# TK90X.net
KiCad netlist of a schematic drawn in EAGLE
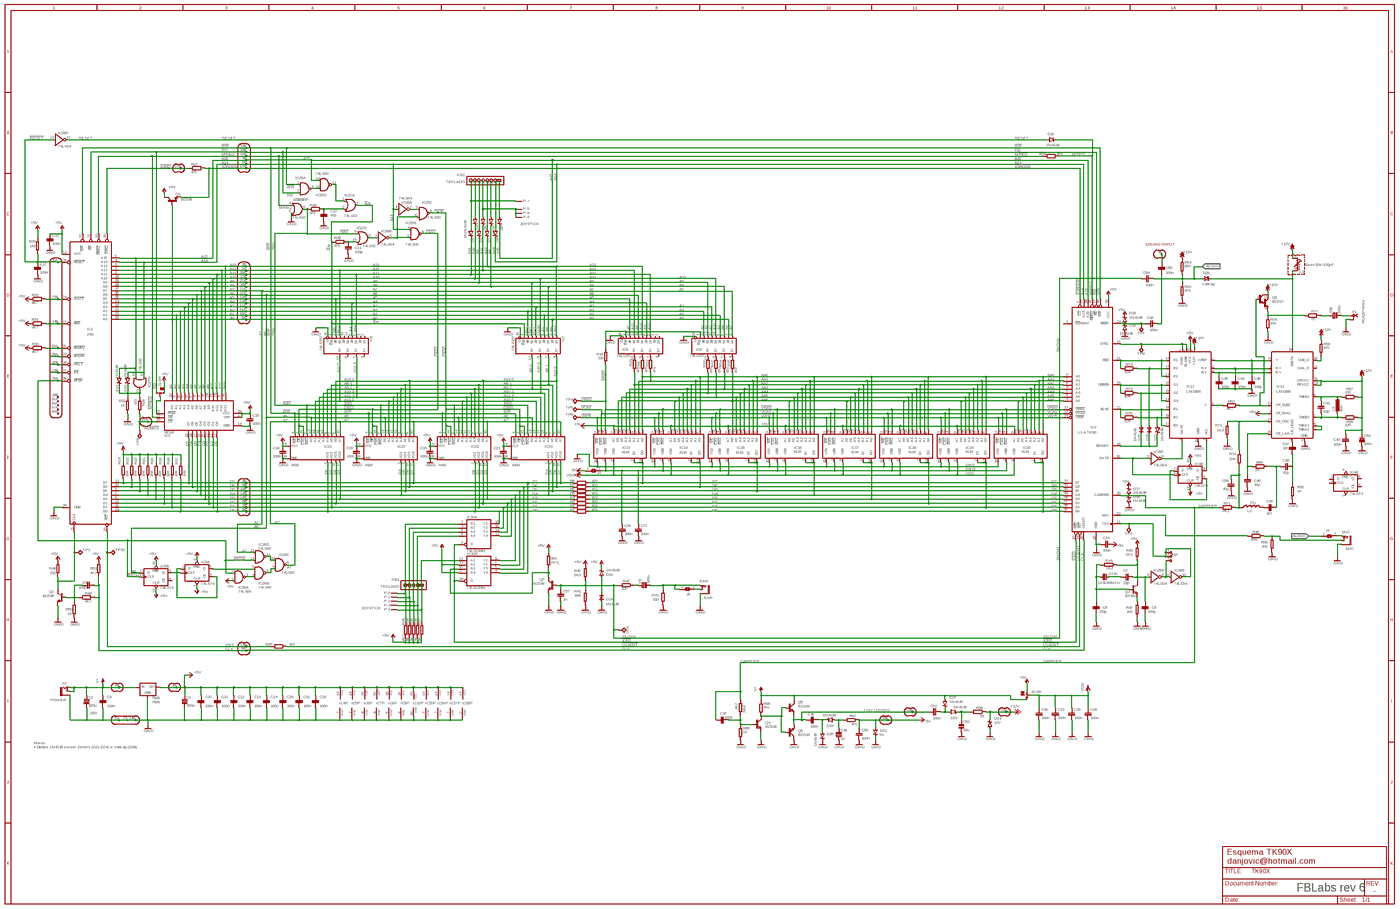
[diagram p0: schematic, sheet 1, overview]
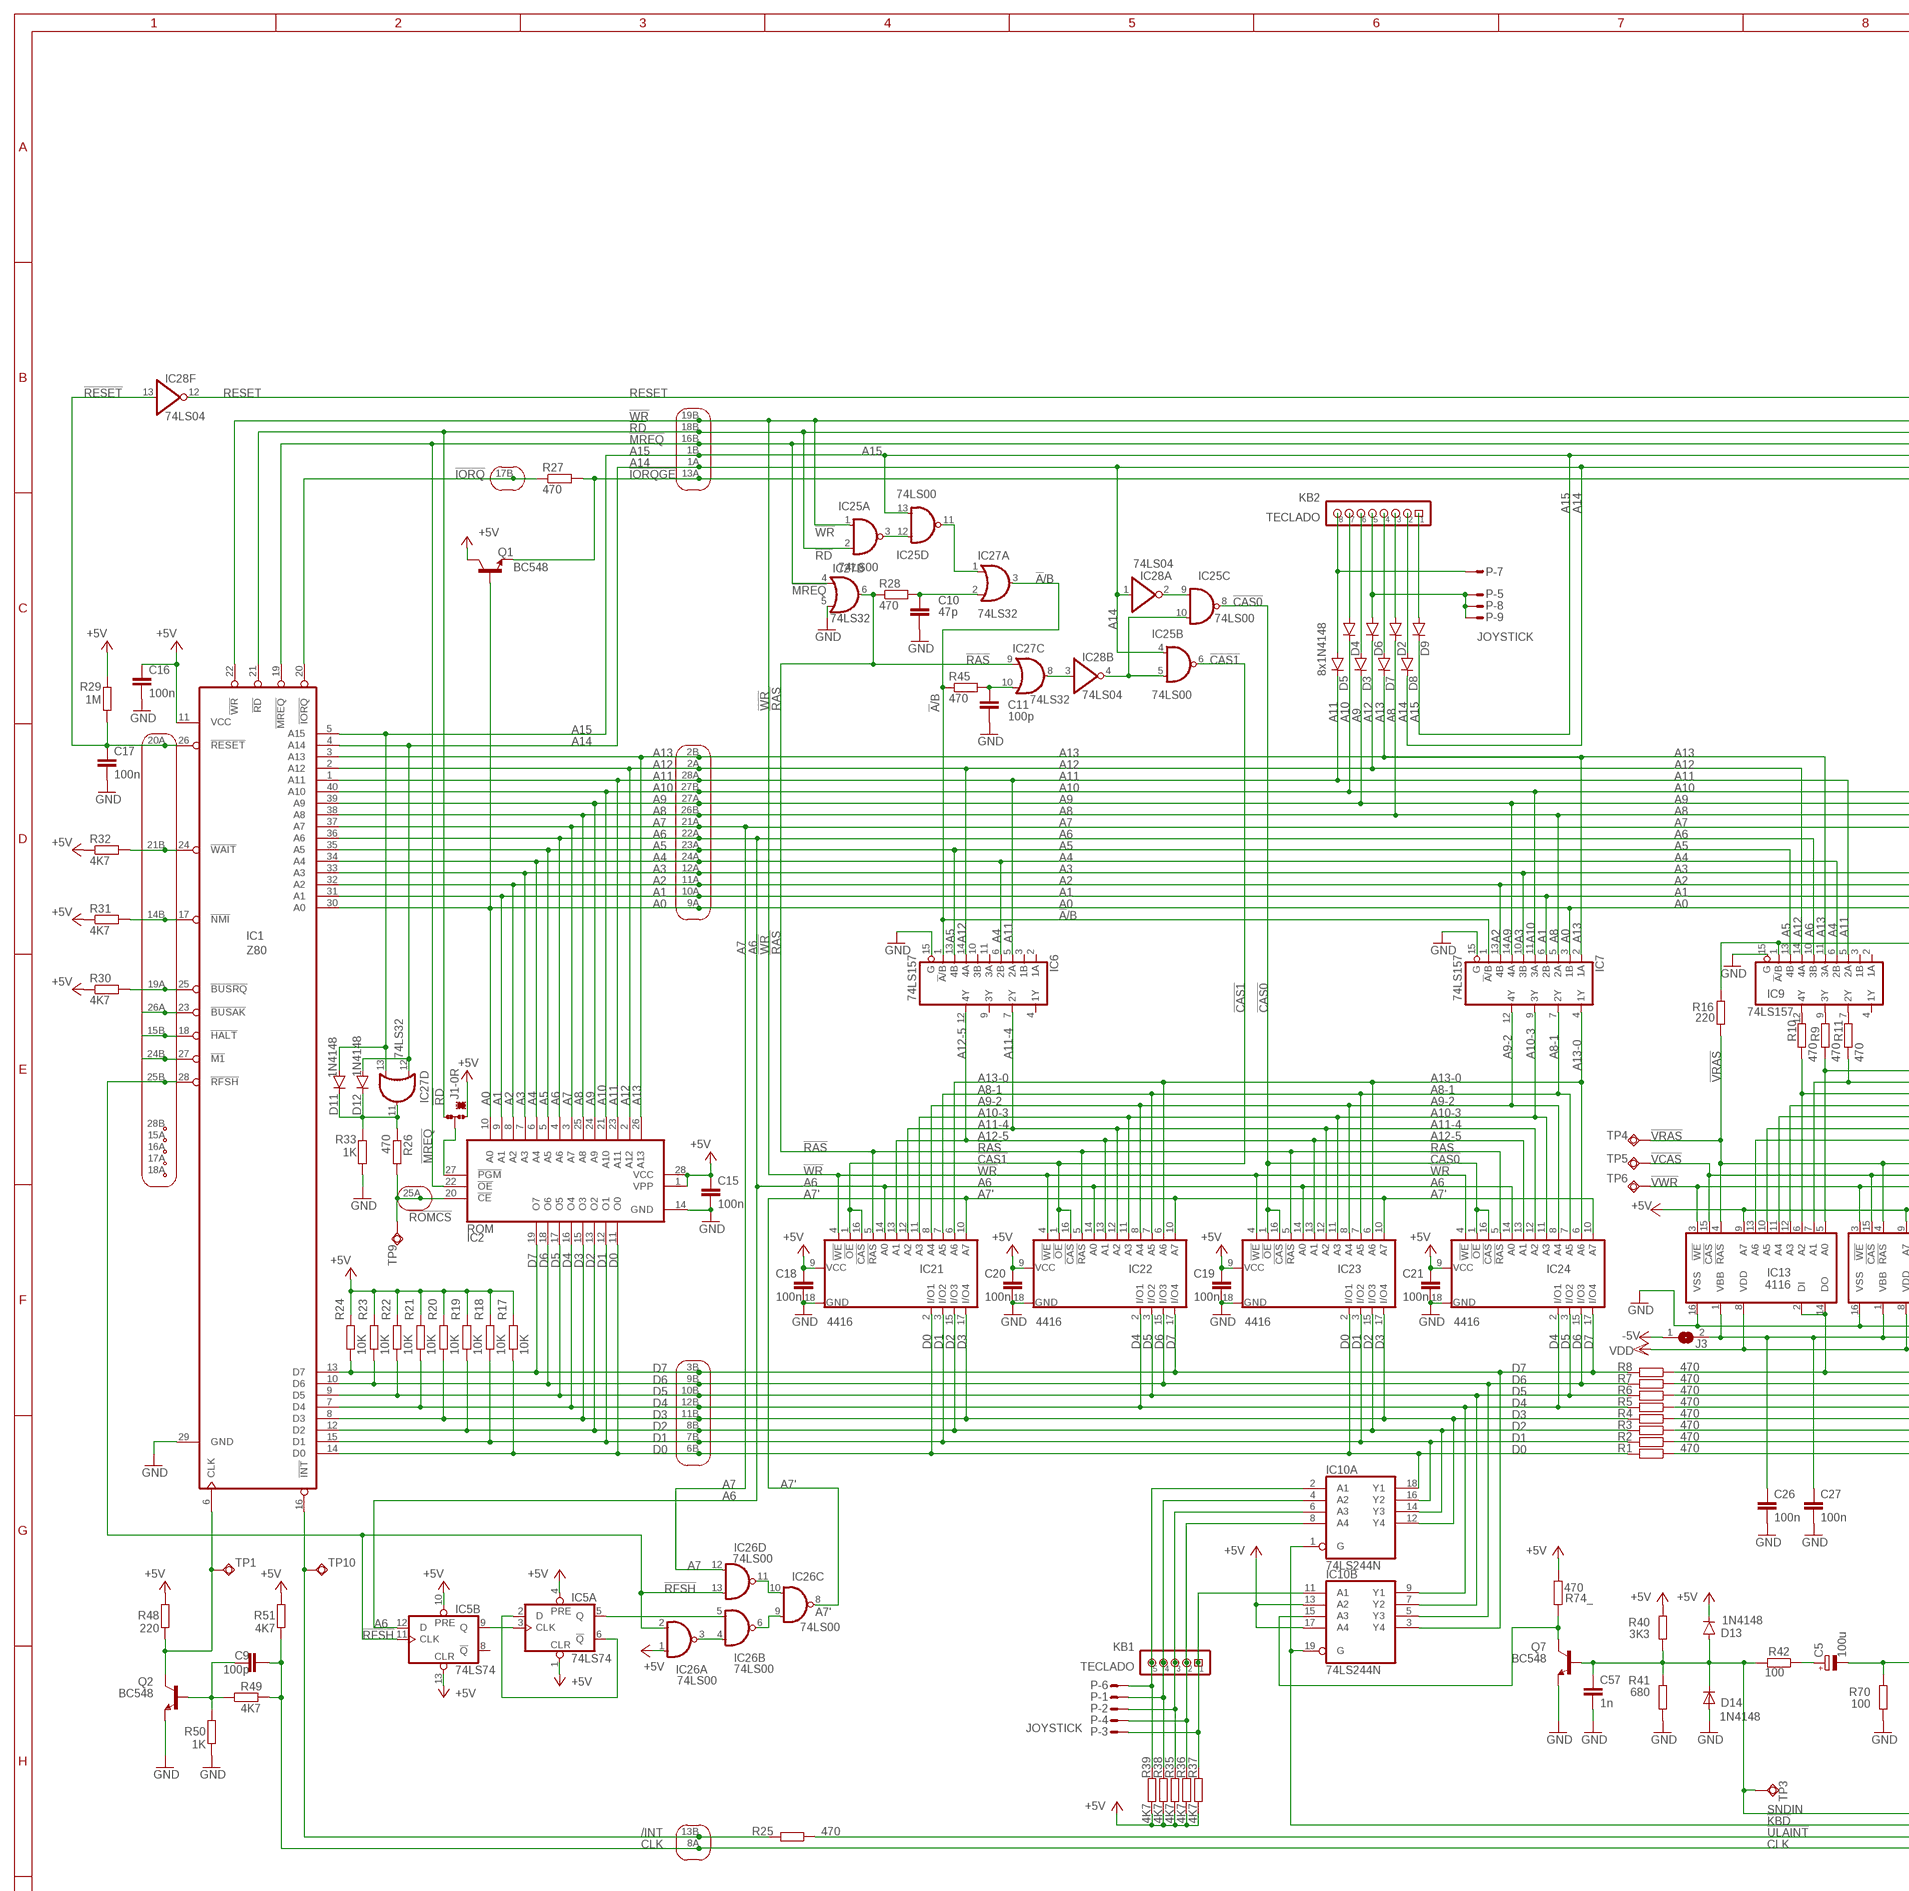
[diagram p1: schematic, sheet 1, part 1 of 4]
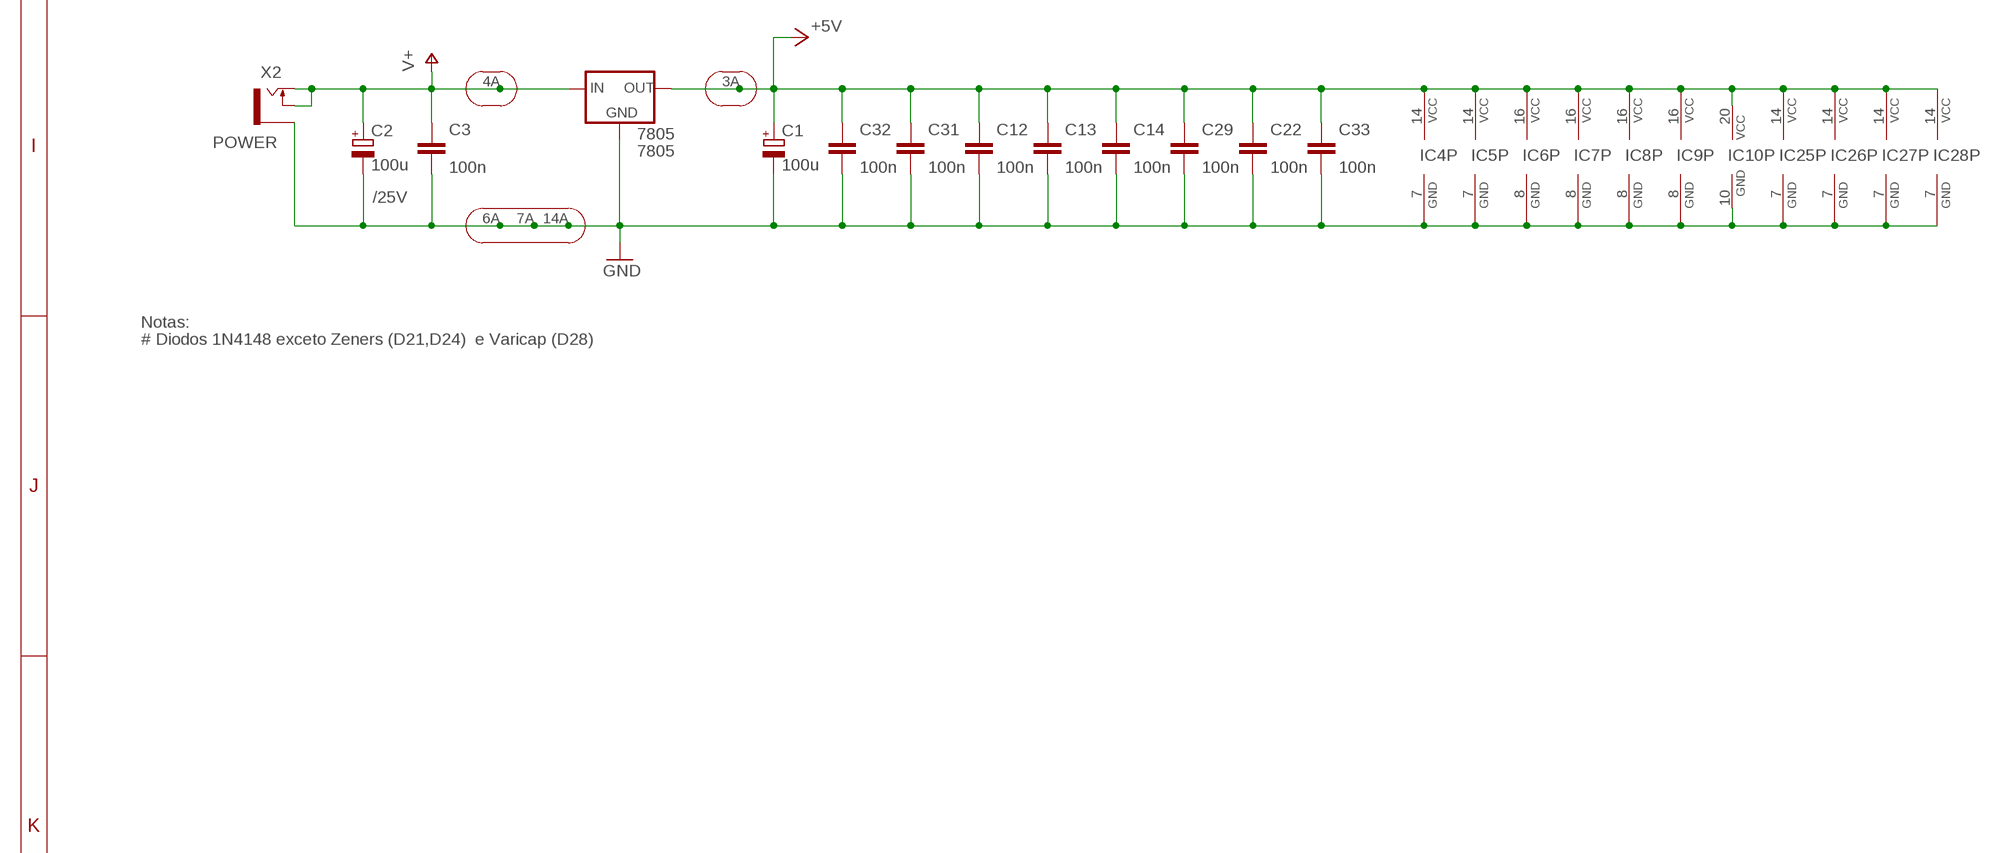
[diagram p2: schematic, sheet 1, part 2 of 4]
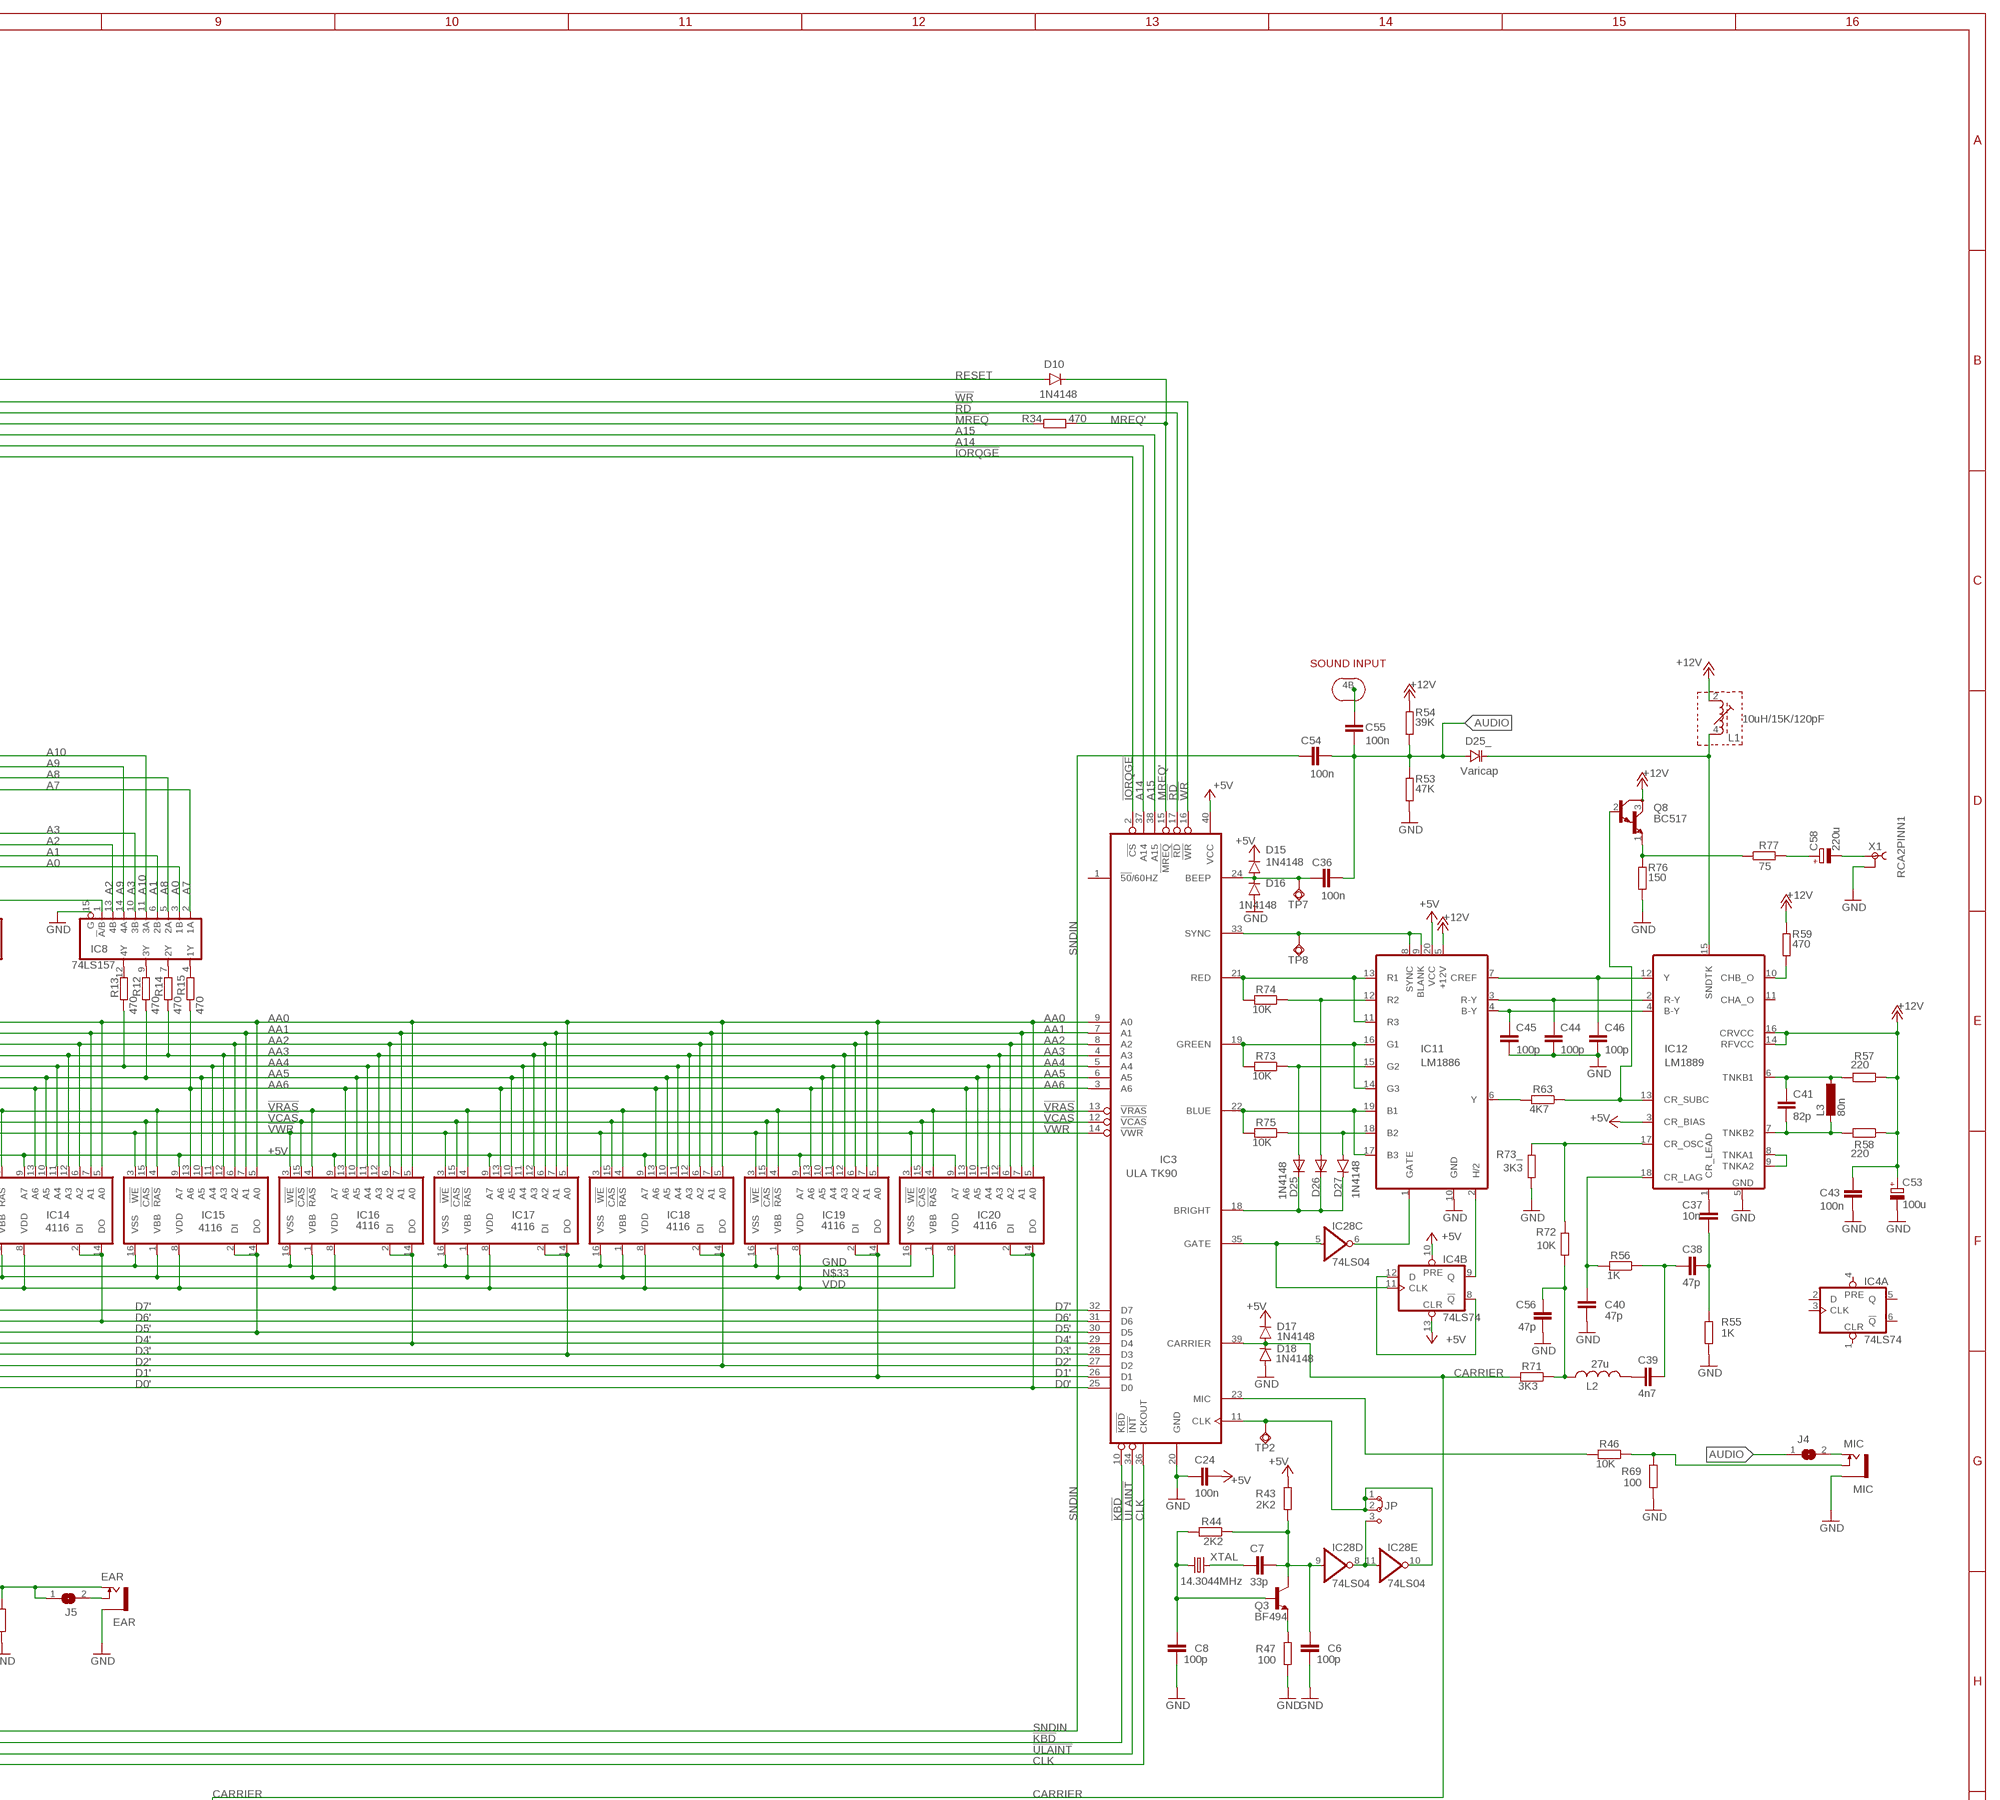
[diagram p3: schematic, sheet 1, part 3 of 4]
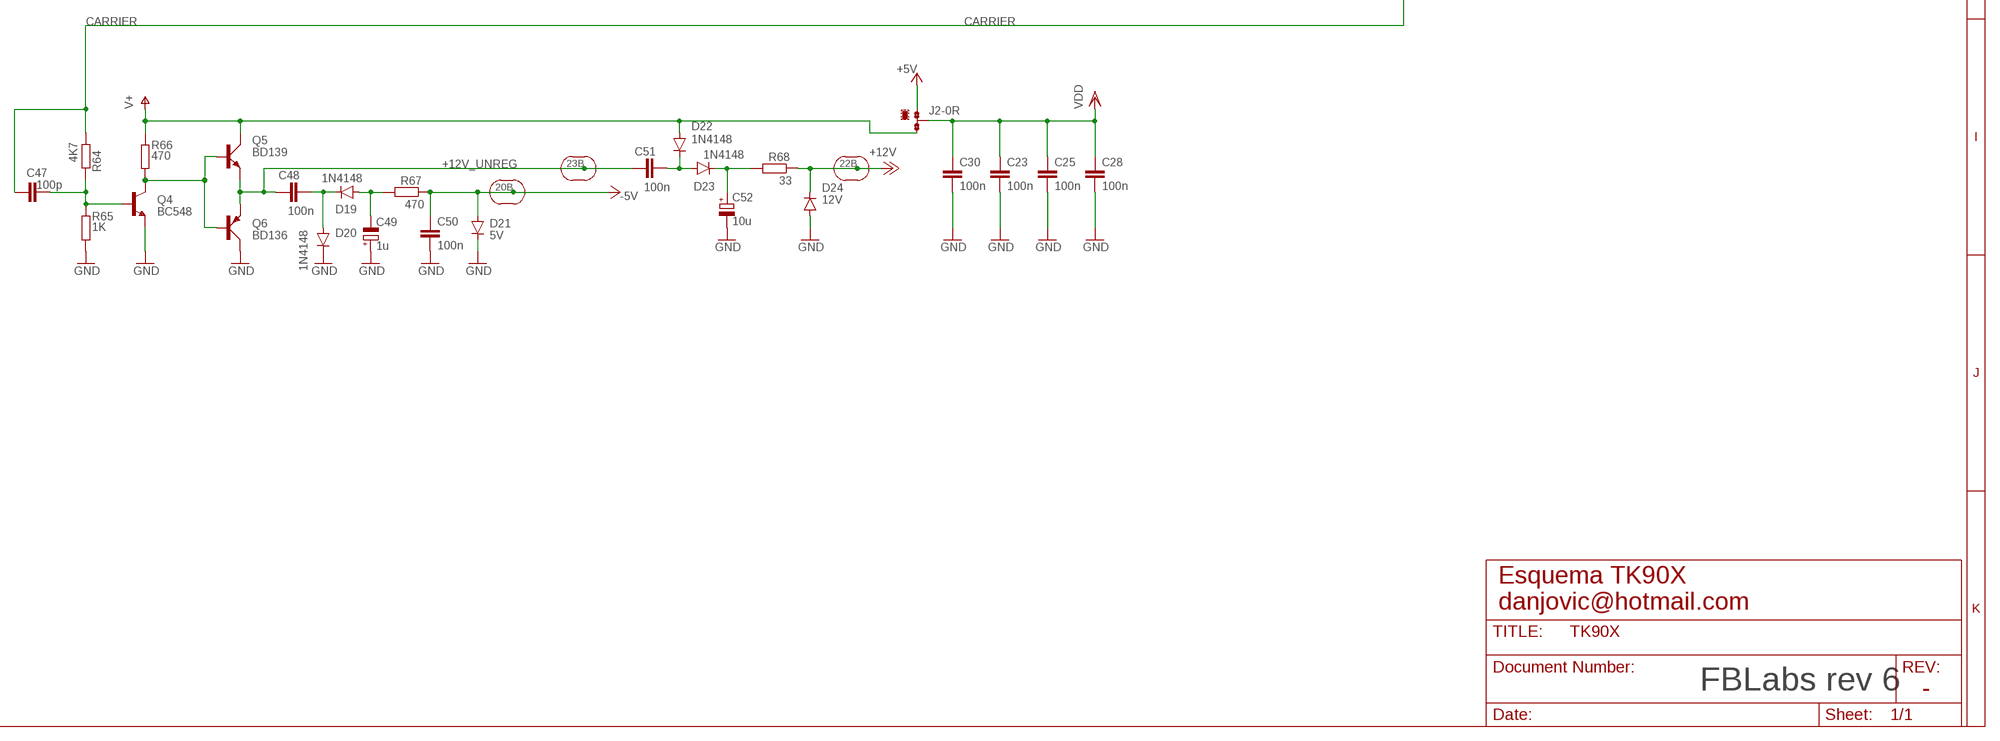
[diagram p4: schematic, sheet 1, part 4 of 4]

(export (version "E")
  (design (tool "Eeschema 10.0.6"))
  (components
    (comp (ref "7805")
      (value "7805")
      (footprint "eagle-import:78XXL")
      (libsource (lib "eagle-import") (part "78XXL"))
    )
    (comp (ref "C1")
      (value "100u")
      (footprint "eagle-import:E5-8,5")
      (libsource (lib "eagle-import") (part "CPOL-EUE5-8.5"))
    )
    (comp (ref "C2")
      (value "100u")
      (footprint "eagle-import:E5-8,5")
      (libsource (lib "eagle-import") (part "CPOL-EUE5-8.5"))
    )
    (comp (ref "C3")
      (value "100n")
      (footprint "eagle-import:C050-024X044")
      (libsource (lib "eagle-import") (part "C-EU050-024X044"))
    )
    (comp (ref "C5")
      (value "100u")
      (footprint "eagle-import:E5-4")
      (libsource (lib "eagle-import") (part "CPOL-EUE5-4"))
    )
    (comp (ref "C6")
      (value "100p")
      (footprint "eagle-import:C050-024X044")
      (libsource (lib "eagle-import") (part "C-EU050-024X044"))
    )
    (comp (ref "C7")
      (value "33p")
      (footprint "eagle-import:C050-024X044")
      (libsource (lib "eagle-import") (part "C-EU050-024X044"))
    )
    (comp (ref "C8")
      (value "100p")
      (footprint "eagle-import:C050-024X044")
      (libsource (lib "eagle-import") (part "C-EU050-024X044"))
    )
    (comp (ref "C9")
      (value "100p")
      (footprint "eagle-import:C050-024X044")
      (libsource (lib "eagle-import") (part "C-EU050-024X044"))
    )
    (comp (ref "C10")
      (value "47p")
      (footprint "eagle-import:C050-024X044")
      (libsource (lib "eagle-import") (part "C-EU050-024X044"))
    )
    (comp (ref "C11")
      (value "100p")
      (footprint "eagle-import:C050-024X044")
      (libsource (lib "eagle-import") (part "C-EU050-024X044"))
    )
    (comp (ref "C12")
      (value "100n")
      (footprint "eagle-import:C050-024X044")
      (libsource (lib "eagle-import") (part "C-EU050-024X044"))
    )
    (comp (ref "C13")
      (value "100n")
      (footprint "eagle-import:C050-024X044")
      (libsource (lib "eagle-import") (part "C-EU050-024X044"))
    )
    (comp (ref "C14")
      (value "100n")
      (footprint "eagle-import:C050-024X044")
      (libsource (lib "eagle-import") (part "C-EU050-024X044"))
    )
    (comp (ref "C15")
      (value "100n")
      (footprint "eagle-import:C050-024X044")
      (libsource (lib "eagle-import") (part "C-EU050-024X044"))
    )
    (comp (ref "C16")
      (value "100n")
      (footprint "eagle-import:C050-024X044")
      (libsource (lib "eagle-import") (part "C-EU050-024X044"))
    )
    (comp (ref "C17")
      (value "100n")
      (footprint "eagle-import:C050-024X044")
      (libsource (lib "eagle-import") (part "C-EU050-024X044"))
    )
    (comp (ref "C18")
      (value "100n")
      (footprint "eagle-import:C050-024X044")
      (libsource (lib "eagle-import") (part "C-EU050-024X044"))
    )
    (comp (ref "C19")
      (value "100n")
      (footprint "eagle-import:C050-024X044")
      (libsource (lib "eagle-import") (part "C-EU050-024X044"))
    )
    (comp (ref "C20")
      (value "100n")
      (footprint "eagle-import:C050-024X044")
      (libsource (lib "eagle-import") (part "C-EU050-024X044"))
    )
    (comp (ref "C21")
      (value "100n")
      (footprint "eagle-import:C050-024X044")
      (libsource (lib "eagle-import") (part "C-EU050-024X044"))
    )
    (comp (ref "C22")
      (value "100n")
      (footprint "eagle-import:C050-024X044")
      (libsource (lib "eagle-import") (part "C-EU050-024X044"))
    )
    (comp (ref "C23")
      (value "100n")
      (footprint "eagle-import:C050-024X044")
      (libsource (lib "eagle-import") (part "C-EU050-024X044"))
    )
    (comp (ref "C24")
      (value "100n")
      (footprint "eagle-import:C050-024X044")
      (libsource (lib "eagle-import") (part "C-EU050-024X044"))
    )
    (comp (ref "C25")
      (value "100n")
      (footprint "eagle-import:C050-024X044")
      (libsource (lib "eagle-import") (part "C-EU050-024X044"))
    )
    (comp (ref "C26")
      (value "100n")
      (footprint "eagle-import:C050-024X044")
      (libsource (lib "eagle-import") (part "C-EU050-024X044"))
    )
    (comp (ref "C27")
      (value "100n")
      (footprint "eagle-import:C050-024X044")
      (libsource (lib "eagle-import") (part "C-EU050-024X044"))
    )
    (comp (ref "C28")
      (value "100n")
      (footprint "eagle-import:C050-024X044")
      (libsource (lib "eagle-import") (part "C-EU050-024X044"))
    )
    (comp (ref "C29")
      (value "100n")
      (footprint "eagle-import:C050-024X044")
      (libsource (lib "eagle-import") (part "C-EU050-024X044"))
    )
    (comp (ref "C30")
      (value "100n")
      (footprint "eagle-import:C050-024X044")
      (libsource (lib "eagle-import") (part "C-EU050-024X044"))
    )
    (comp (ref "C31")
      (value "100n")
      (footprint "eagle-import:C050-024X044")
      (libsource (lib "eagle-import") (part "C-EU050-024X044"))
    )
    (comp (ref "C32")
      (value "100n")
      (footprint "eagle-import:C050-024X044")
      (libsource (lib "eagle-import") (part "C-EU050-024X044"))
    )
    (comp (ref "C33")
      (value "100n")
      (footprint "eagle-import:C050-024X044")
      (libsource (lib "eagle-import") (part "C-EU050-024X044"))
    )
    (comp (ref "C36")
      (value "100n")
      (footprint "eagle-import:C050-024X044")
      (libsource (lib "eagle-import") (part "C-EU050-024X044"))
    )
    (comp (ref "C37")
      (value "10n")
      (footprint "eagle-import:C050-024X044")
      (libsource (lib "eagle-import") (part "C-EU050-024X044"))
    )
    (comp (ref "C38")
      (value "47p")
      (footprint "eagle-import:C050-024X044")
      (libsource (lib "eagle-import") (part "C-EU050-024X044"))
    )
    (comp (ref "C39")
      (value "4n7")
      (footprint "eagle-import:C050-024X044")
      (libsource (lib "eagle-import") (part "C-EU050-024X044"))
    )
    (comp (ref "C40")
      (value "47p")
      (footprint "eagle-import:C050-024X044")
      (libsource (lib "eagle-import") (part "C-EU050-024X044"))
    )
    (comp (ref "C41")
      (value "82p")
      (footprint "eagle-import:C050-024X044")
      (libsource (lib "eagle-import") (part "C-EU050-024X044"))
    )
    (comp (ref "C43")
      (value "100n")
      (footprint "eagle-import:C050-024X044")
      (libsource (lib "eagle-import") (part "C-EU050-024X044"))
    )
    (comp (ref "C44")
      (value "100p")
      (footprint "eagle-import:C050-024X044")
      (libsource (lib "eagle-import") (part "C-EU050-024X044"))
    )
    (comp (ref "C45")
      (value "100p")
      (footprint "eagle-import:C050-024X044")
      (libsource (lib "eagle-import") (part "C-EU050-024X044"))
    )
    (comp (ref "C46")
      (value "100p")
      (footprint "eagle-import:C050-024X044")
      (libsource (lib "eagle-import") (part "C-EU050-024X044"))
    )
    (comp (ref "C47")
      (value "100p")
      (footprint "eagle-import:C050-024X044")
      (libsource (lib "eagle-import") (part "C-EU050-024X044"))
    )
    (comp (ref "C48")
      (value "100n")
      (footprint "eagle-import:C050-024X044")
      (libsource (lib "eagle-import") (part "C-EU050-024X044"))
    )
    (comp (ref "C49")
      (value "1u")
      (footprint "eagle-import:E2-4")
      (libsource (lib "eagle-import") (part "CPOL-EUE2-4"))
    )
    (comp (ref "C50")
      (value "100n")
      (footprint "eagle-import:C050-024X044")
      (libsource (lib "eagle-import") (part "C-EU050-024X044"))
    )
    (comp (ref "C51")
      (value "100n")
      (footprint "eagle-import:C050-024X044")
      (libsource (lib "eagle-import") (part "C-EU050-024X044"))
    )
    (comp (ref "C52")
      (value "10u")
      (footprint "eagle-import:E2-5")
      (libsource (lib "eagle-import") (part "CPOL-EUE2-5"))
    )
    (comp (ref "C53")
      (value "100u")
      (footprint "eagle-import:E5-4")
      (libsource (lib "eagle-import") (part "CPOL-EUE5-4"))
    )
    (comp (ref "C54")
      (value "100n")
      (footprint "eagle-import:C050-024X044")
      (libsource (lib "eagle-import") (part "C-EU050-024X044"))
    )
    (comp (ref "C55")
      (value "100n")
      (footprint "eagle-import:C050-024X044")
      (libsource (lib "eagle-import") (part "C-EU050-024X044"))
    )
    (comp (ref "C56")
      (value "47p")
      (footprint "eagle-import:C050-024X044")
      (libsource (lib "eagle-import") (part "C-EU050-024X044"))
    )
    (comp (ref "C57")
      (value "1n")
      (footprint "eagle-import:C050-024X044")
      (libsource (lib "eagle-import") (part "C-EU050-024X044"))
    )
    (comp (ref "C58")
      (value "220u")
      (footprint "eagle-import:E5-6")
      (libsource (lib "eagle-import") (part "CPOL-EUE5-6"))
    )
    (comp (ref "D2")
      (value "1N4148")
      (footprint "eagle-import:DO35-12")
      (libsource (lib "eagle-import") (part "DDO35-12"))
    )
    (comp (ref "D3")
      (value "1N4148")
      (footprint "eagle-import:DO35-12")
      (libsource (lib "eagle-import") (part "DDO35-12"))
    )
    (comp (ref "D4")
      (value "1N4148")
      (footprint "eagle-import:DO35-12")
      (libsource (lib "eagle-import") (part "DDO35-12"))
    )
    (comp (ref "D5")
      (value "1N4148")
      (footprint "eagle-import:DO35-12")
      (libsource (lib "eagle-import") (part "DDO35-12"))
    )
    (comp (ref "D6")
      (value "1N4148")
      (footprint "eagle-import:DO35-12")
      (libsource (lib "eagle-import") (part "DDO35-12"))
    )
    (comp (ref "D7")
      (value "1N4148")
      (footprint "eagle-import:DO35-12")
      (libsource (lib "eagle-import") (part "DDO35-12"))
    )
    (comp (ref "D8")
      (value "1N4148")
      (footprint "eagle-import:DO35-12")
      (libsource (lib "eagle-import") (part "DDO35-12"))
    )
    (comp (ref "D9")
      (value "1N4148")
      (footprint "eagle-import:DO35-12")
      (libsource (lib "eagle-import") (part "DDO35-12"))
    )
    (comp (ref "D10")
      (value "1N4148")
      (footprint "eagle-import:DO35-12")
      (libsource (lib "eagle-import") (part "DDO35-12"))
    )
    (comp (ref "D11")
      (value "1N4148")
      (footprint "eagle-import:DO35-12")
      (libsource (lib "eagle-import") (part "DDO35-12"))
    )
    (comp (ref "D12")
      (value "1N4148")
      (footprint "eagle-import:DO35-12")
      (libsource (lib "eagle-import") (part "DDO35-12"))
    )
    (comp (ref "D13")
      (value "1N4148")
      (footprint "eagle-import:DO35-12")
      (libsource (lib "eagle-import") (part "DDO35-12"))
    )
    (comp (ref "D14")
      (value "1N4148")
      (footprint "eagle-import:D-5")
      (libsource (lib "eagle-import") (part "DIODE-D-5"))
    )
    (comp (ref "D15")
      (value "1N4148")
      (footprint "eagle-import:DO35-12")
      (libsource (lib "eagle-import") (part "DDO35-12"))
    )
    (comp (ref "D16")
      (value "1N4148")
      (footprint "eagle-import:DO35-12")
      (libsource (lib "eagle-import") (part "DDO35-12"))
    )
    (comp (ref "D17")
      (value "1N4148")
      (footprint "eagle-import:DO35-12")
      (libsource (lib "eagle-import") (part "DDO35-12"))
    )
    (comp (ref "D18")
      (value "1N4148")
      (footprint "eagle-import:DO35-12")
      (libsource (lib "eagle-import") (part "DDO35-12"))
    )
    (comp (ref "D19")
      (value "1N4148")
      (footprint "eagle-import:DO35-12")
      (libsource (lib "eagle-import") (part "DDO35-12"))
    )
    (comp (ref "D20")
      (value "1N4148")
      (footprint "eagle-import:DO35-12")
      (libsource (lib "eagle-import") (part "DDO35-12"))
    )
    (comp (ref "D21")
      (value "5V")
      (footprint "eagle-import:DO35-12")
      (libsource (lib "eagle-import") (part "DDO35-12"))
    )
    (comp (ref "D22")
      (value "1N4148")
      (footprint "eagle-import:DO35-12")
      (libsource (lib "eagle-import") (part "DDO35-12"))
    )
    (comp (ref "D23")
      (value "1N4148")
      (footprint "eagle-import:DO35-12")
      (libsource (lib "eagle-import") (part "DDO35-12"))
    )
    (comp (ref "D24")
      (value "12V")
      (footprint "eagle-import:DO35-12")
      (libsource (lib "eagle-import") (part "DDO35-12"))
    )
    (comp (ref "D25")
      (value "1N4148")
      (footprint "eagle-import:D-5")
      (libsource (lib "eagle-import") (part "DIODE-D-5"))
    )
    (comp (ref "D25_")
      (value "Varicap")
      (footprint "eagle-import:D200")
      (libsource (lib "eagle-import") (part "VARICAP-200"))
    )
    (comp (ref "D26")
      (value "1N4148")
      (footprint "eagle-import:D-5")
      (libsource (lib "eagle-import") (part "DIODE-D-5"))
    )
    (comp (ref "D27")
      (value "1N4148")
      (footprint "eagle-import:DO35-12")
      (libsource (lib "eagle-import") (part "DDO35-12"))
    )
    (comp (ref "EAR")
      (value "EAR")
      (footprint "eagle-import:MONO")
      (libsource (lib "eagle-import") (part "JACK?-MONO"))
    )
    (comp (ref "IC1")
      (value "Z80")
      (footprint "eagle-import:DIL40")
      (libsource (lib "eagle-import") (part "Z80CPU"))
    )
    (comp (ref "IC2")
      (value "ROM")
      (footprint "eagle-import:DIL28")
      (libsource (lib "eagle-import") (part "25128"))
    )
    (comp (ref "IC3")
      (value "ULA TK90")
      (footprint "eagle-import:DIL40")
      (libsource (lib "eagle-import") (part "ULA-TK90"))
    )
    (comp (ref "IC4")
      (value "74LS74")
      (footprint "eagle-import:DIL14")
      (libsource (lib "eagle-import") (part "7474NLS"))
    )
    (comp (ref "IC5")
      (value "74LS74")
      (footprint "eagle-import:DIL14")
      (libsource (lib "eagle-import") (part "7474NLS"))
    )
    (comp (ref "IC6")
      (value "74LS157")
      (footprint "eagle-import:DIL16")
      (libsource (lib "eagle-import") (part "74157NS"))
    )
    (comp (ref "IC7")
      (value "74LS157")
      (footprint "eagle-import:DIL16")
      (libsource (lib "eagle-import") (part "74157NS"))
    )
    (comp (ref "IC8")
      (value "74LS157")
      (footprint "eagle-import:DIL16")
      (libsource (lib "eagle-import") (part "74157NS"))
    )
    (comp (ref "IC9")
      (value "74LS157")
      (footprint "eagle-import:DIL16")
      (libsource (lib "eagle-import") (part "74157NS"))
    )
    (comp (ref "IC10")
      (value "74LS244N")
      (footprint "eagle-import:DIL20")
      (libsource (lib "eagle-import") (part "74244NLS"))
    )
    (comp (ref "IC11")
      (value "LM1886")
      (footprint "eagle-import:DIL20")
      (libsource (lib "eagle-import") (part "LM1886N"))
    )
    (comp (ref "IC12")
      (value "LM1889")
      (footprint "eagle-import:DIL18")
      (libsource (lib "eagle-import") (part "LM1889"))
    )
    (comp (ref "IC13")
      (value "4116")
      (footprint "eagle-import:DIL16")
      (libsource (lib "eagle-import") (part "MK4516"))
    )
    (comp (ref "IC14")
      (value "4116")
      (footprint "eagle-import:DIL16")
      (libsource (lib "eagle-import") (part "MK4516"))
    )
    (comp (ref "IC15")
      (value "4116")
      (footprint "eagle-import:DIL16")
      (libsource (lib "eagle-import") (part "MK4516"))
    )
    (comp (ref "IC16")
      (value "4116")
      (footprint "eagle-import:DIL16")
      (libsource (lib "eagle-import") (part "MK4516"))
    )
    (comp (ref "IC17")
      (value "4116")
      (footprint "eagle-import:DIL16")
      (libsource (lib "eagle-import") (part "MK4516"))
    )
    (comp (ref "IC18")
      (value "4116")
      (footprint "eagle-import:DIL16")
      (libsource (lib "eagle-import") (part "MK4516"))
    )
    (comp (ref "IC19")
      (value "4116")
      (footprint "eagle-import:DIL16")
      (libsource (lib "eagle-import") (part "MK4516"))
    )
    (comp (ref "IC20")
      (value "4116")
      (footprint "eagle-import:DIL16")
      (libsource (lib "eagle-import") (part "MK4516"))
    )
    (comp (ref "IC21")
      (value "4416")
      (footprint "eagle-import:DIL18")
      (libsource (lib "eagle-import") (part "4416"))
    )
    (comp (ref "IC22")
      (value "4416")
      (footprint "eagle-import:DIL18")
      (libsource (lib "eagle-import") (part "4416"))
    )
    (comp (ref "IC23")
      (value "4416")
      (footprint "eagle-import:DIL18")
      (libsource (lib "eagle-import") (part "4416"))
    )
    (comp (ref "IC24")
      (value "4416")
      (footprint "eagle-import:DIL18")
      (libsource (lib "eagle-import") (part "4416"))
    )
    (comp (ref "IC25")
      (value "74LS00")
      (footprint "eagle-import:DIL14")
      (libsource (lib "eagle-import") (part "7400NLS"))
    )
    (comp (ref "IC26")
      (value "74LS00")
      (footprint "eagle-import:DIL14")
      (libsource (lib "eagle-import") (part "7400NLS"))
    )
    (comp (ref "IC27")
      (value "74LS32")
      (footprint "eagle-import:DIL14")
      (libsource (lib "eagle-import") (part "7432NLS"))
    )
    (comp (ref "IC28")
      (value "74LS04")
      (footprint "eagle-import:DIL14")
      (libsource (lib "eagle-import") (part "7404NLS"))
    )
    (comp (ref "J1")
      (value "0R-JUMPB")
      (footprint "eagle-import:B0R-JMP")
      (libsource (lib "eagle-import") (part "0R-JUMPB"))
    )
    (comp (ref "J2")
      (value "0R-JUMPB")
      (footprint "eagle-import:B0R-JMP")
      (libsource (lib "eagle-import") (part "0R-JUMPB"))
    )
    (comp (ref "J3") (value "SJ") (footprint "eagle-import:SJ") (libsource (lib "eagle-import") (part "SJ")))
    (comp (ref "J4") (value "SJ") (footprint "eagle-import:SJ") (libsource (lib "eagle-import") (part "SJ")))
    (comp (ref "J5") (value "SJ") (footprint "eagle-import:SJ") (libsource (lib "eagle-import") (part "SJ")))
    (comp (ref "JP")
      (value "J2X1MM")
      (footprint "eagle-import:03C")
      (libsource (lib "eagle-import") (part "J2X1MM"))
    )
    (comp (ref "KB1")
      (value "TECLADO")
      (footprint "eagle-import:FE05-1")
      (libsource (lib "eagle-import") (part "CON-TECL-5"))
    )
    (comp (ref "KB2")
      (value "TECLADO")
      (footprint "eagle-import:FE08")
      (libsource (lib "eagle-import") (part "CON-TECL-8"))
    )
    (comp (ref "L1")
      (value "10uH/15K/120pF")
      (footprint "eagle-import:COIL")
      (libsource (lib "eagle-import") (part "COIL"))
    )
    (comp (ref "L2")
      (value "27u")
      (footprint "eagle-import:0207_7")
      (libsource (lib "eagle-import") (part "L-US0207/7"))
    )
    (comp (ref "L3")
      (value "80n")
      (footprint "eagle-import:0204_5")
      (libsource (lib "eagle-import") (part "L-EU0204/5"))
    )
    (comp (ref "MIC")
      (value "MIC")
      (footprint "eagle-import:MONO")
      (libsource (lib "eagle-import") (part "JACK?-MONO"))
    )
    (comp (ref "P")
      (value "JOYSTICK")
      (footprint "eagle-import:177-009-MALE")
      (libsource (lib "eagle-import") (part "M09?S.590"))
    )
    (comp (ref "Q1")
      (value "BC548")
      (footprint "eagle-import:TO92L")
      (libsource (lib "eagle-import") (part "-NPN-TO92L"))
    )
    (comp (ref "Q2")
      (value "BC548")
      (footprint "eagle-import:TO92L")
      (libsource (lib "eagle-import") (part "-NPN-TO92L"))
    )
    (comp (ref "Q3")
      (value "BF494")
      (footprint "eagle-import:TO92-CEB")
      (libsource (lib "eagle-import") (part "BF494"))
    )
    (comp (ref "Q4")
      (value "BC548")
      (footprint "eagle-import:TO92L")
      (libsource (lib "eagle-import") (part "-NPN-TO92L"))
    )
    (comp (ref "Q5")
      (value "BD139")
      (footprint "eagle-import:TO126AV")
      (libsource (lib "eagle-import") (part "BD139"))
    )
    (comp (ref "Q6")
      (value "BD136")
      (footprint "eagle-import:TO126AV")
      (libsource (lib "eagle-import") (part "BD140"))
    )
    (comp (ref "Q7")
      (value "BC548")
      (footprint "eagle-import:TO92L")
      (libsource (lib "eagle-import") (part "-NPN-TO92L"))
    )
    (comp (ref "Q8")
      (value "BC517")
      (footprint "eagle-import:TO92")
      (libsource (lib "eagle-import") (part "BC517"))
    )
    (comp (ref "R1")
      (value "470")
      (footprint "eagle-import:0207_12")
      (libsource (lib "eagle-import") (part "R-EU_0207/12"))
    )
    (comp (ref "R2")
      (value "470")
      (footprint "eagle-import:0207_12")
      (libsource (lib "eagle-import") (part "R-EU_0207/12"))
    )
    (comp (ref "R3")
      (value "470")
      (footprint "eagle-import:0207_12")
      (libsource (lib "eagle-import") (part "R-EU_0207/12"))
    )
    (comp (ref "R4")
      (value "470")
      (footprint "eagle-import:0207_12")
      (libsource (lib "eagle-import") (part "R-EU_0207/12"))
    )
    (comp (ref "R5")
      (value "470")
      (footprint "eagle-import:0207_12")
      (libsource (lib "eagle-import") (part "R-EU_0207/12"))
    )
    (comp (ref "R6")
      (value "470")
      (footprint "eagle-import:0207_12")
      (libsource (lib "eagle-import") (part "R-EU_0207/12"))
    )
    (comp (ref "R7")
      (value "470")
      (footprint "eagle-import:0207_12")
      (libsource (lib "eagle-import") (part "R-EU_0207/12"))
    )
    (comp (ref "R8")
      (value "470")
      (footprint "eagle-import:0207_12")
      (libsource (lib "eagle-import") (part "R-EU_0207/12"))
    )
    (comp (ref "R9")
      (value "470")
      (footprint "eagle-import:0207_12")
      (libsource (lib "eagle-import") (part "R-EU_0207/12"))
    )
    (comp (ref "R10")
      (value "470")
      (footprint "eagle-import:0207_12")
      (libsource (lib "eagle-import") (part "R-EU_0207/12"))
    )
    (comp (ref "R11")
      (value "470")
      (footprint "eagle-import:0207_12")
      (libsource (lib "eagle-import") (part "R-EU_0207/12"))
    )
    (comp (ref "R12")
      (value "470")
      (footprint "eagle-import:0207_12")
      (libsource (lib "eagle-import") (part "R-EU_0207/12"))
    )
    (comp (ref "R13")
      (value "470")
      (footprint "eagle-import:0207_12")
      (libsource (lib "eagle-import") (part "R-EU_0207/12"))
    )
    (comp (ref "R14")
      (value "470")
      (footprint "eagle-import:0207_12")
      (libsource (lib "eagle-import") (part "R-EU_0207/12"))
    )
    (comp (ref "R15")
      (value "470")
      (footprint "eagle-import:0207_12")
      (libsource (lib "eagle-import") (part "R-EU_0207/12"))
    )
    (comp (ref "R16")
      (value "220")
      (footprint "eagle-import:0207_12")
      (libsource (lib "eagle-import") (part "R-EU_0207/12"))
    )
    (comp (ref "R17")
      (value "10K")
      (footprint "eagle-import:0207_12")
      (libsource (lib "eagle-import") (part "R-EU_0207/12"))
    )
    (comp (ref "R18")
      (value "10K")
      (footprint "eagle-import:0207_12")
      (libsource (lib "eagle-import") (part "R-EU_0207/12"))
    )
    (comp (ref "R19")
      (value "10K")
      (footprint "eagle-import:0207_12")
      (libsource (lib "eagle-import") (part "R-EU_0207/12"))
    )
    (comp (ref "R20")
      (value "10K")
      (footprint "eagle-import:0207_12")
      (libsource (lib "eagle-import") (part "R-EU_0207/12"))
    )
    (comp (ref "R21")
      (value "10K")
      (footprint "eagle-import:0207_12")
      (libsource (lib "eagle-import") (part "R-EU_0207/12"))
    )
    (comp (ref "R22")
      (value "10K")
      (footprint "eagle-import:0207_12")
      (libsource (lib "eagle-import") (part "R-EU_0207/12"))
    )
    (comp (ref "R23")
      (value "10K")
      (footprint "eagle-import:0207_12")
      (libsource (lib "eagle-import") (part "R-EU_0207/12"))
    )
    (comp (ref "R24")
      (value "10K")
      (footprint "eagle-import:0207_12")
      (libsource (lib "eagle-import") (part "R-EU_0207/12"))
    )
    (comp (ref "R25")
      (value "470")
      (footprint "eagle-import:0207_12")
      (libsource (lib "eagle-import") (part "R-EU_0207/12"))
    )
    (comp (ref "R26")
      (value "470")
      (footprint "eagle-import:0207_12")
      (libsource (lib "eagle-import") (part "R-EU_0207/12"))
    )
    (comp (ref "R27")
      (value "470")
      (footprint "eagle-import:0207_12")
      (libsource (lib "eagle-import") (part "R-EU_0207/12"))
    )
    (comp (ref "R28")
      (value "470")
      (footprint "eagle-import:0207_12")
      (libsource (lib "eagle-import") (part "R-EU_0207/12"))
    )
    (comp (ref "R29")
      (value "1M")
      (footprint "eagle-import:0207_12")
      (libsource (lib "eagle-import") (part "R-EU_0207/12"))
    )
    (comp (ref "R30")
      (value "4K7")
      (footprint "eagle-import:0207_12")
      (libsource (lib "eagle-import") (part "R-EU_0207/12"))
    )
    (comp (ref "R31")
      (value "4K7")
      (footprint "eagle-import:0207_12")
      (libsource (lib "eagle-import") (part "R-EU_0207/12"))
    )
    (comp (ref "R32")
      (value "4K7")
      (footprint "eagle-import:0207_12")
      (libsource (lib "eagle-import") (part "R-EU_0207/12"))
    )
    (comp (ref "R33")
      (value "1K")
      (footprint "eagle-import:0207_12")
      (libsource (lib "eagle-import") (part "R-EU_0207/12"))
    )
    (comp (ref "R34")
      (value "470")
      (footprint "eagle-import:0207_12")
      (libsource (lib "eagle-import") (part "R-EU_0207/12"))
    )
    (comp (ref "R35")
      (value "4K7")
      (footprint "eagle-import:0207_12")
      (libsource (lib "eagle-import") (part "R-EU_0207/12"))
    )
    (comp (ref "R36")
      (value "4K7")
      (footprint "eagle-import:0207_12")
      (libsource (lib "eagle-import") (part "R-EU_0207/12"))
    )
    (comp (ref "R37")
      (value "4K7")
      (footprint "eagle-import:0207_12")
      (libsource (lib "eagle-import") (part "R-EU_0207/12"))
    )
    (comp (ref "R38")
      (value "4K7")
      (footprint "eagle-import:0207_12")
      (libsource (lib "eagle-import") (part "R-EU_0207/12"))
    )
    (comp (ref "R39")
      (value "4K7")
      (footprint "eagle-import:0207_12")
      (libsource (lib "eagle-import") (part "R-EU_0207/12"))
    )
    (comp (ref "R40")
      (value "3K3")
      (footprint "eagle-import:0207_12")
      (libsource (lib "eagle-import") (part "R-EU_0207/12"))
    )
    (comp (ref "R41")
      (value "680")
      (footprint "eagle-import:0207_5V")
      (libsource (lib "eagle-import") (part "R-EU_0207/5V"))
    )
    (comp (ref "R42")
      (value "100")
      (footprint "eagle-import:0207_5V")
      (libsource (lib "eagle-import") (part "R-EU_0207/5V"))
    )
    (comp (ref "R43")
      (value "2K2")
      (footprint "eagle-import:0207_12")
      (libsource (lib "eagle-import") (part "R-EU_0207/12"))
    )
    (comp (ref "R44")
      (value "2K2")
      (footprint "eagle-import:0207_12")
      (libsource (lib "eagle-import") (part "R-EU_0207/12"))
    )
    (comp (ref "R45")
      (value "470")
      (footprint "eagle-import:0207_12")
      (libsource (lib "eagle-import") (part "R-EU_0207/12"))
    )
    (comp (ref "R46")
      (value "10K")
      (footprint "eagle-import:0207_12")
      (libsource (lib "eagle-import") (part "R-EU_0207/12"))
    )
    (comp (ref "R47")
      (value "100")
      (footprint "eagle-import:0207_12")
      (libsource (lib "eagle-import") (part "R-EU_0207/12"))
    )
    (comp (ref "R48")
      (value "220")
      (footprint "eagle-import:0207_12")
      (libsource (lib "eagle-import") (part "R-EU_0207/12"))
    )
    (comp (ref "R49")
      (value "4K7")
      (footprint "eagle-import:0207_12")
      (libsource (lib "eagle-import") (part "R-EU_0207/12"))
    )
    (comp (ref "R50")
      (value "1K")
      (footprint "eagle-import:0207_12")
      (libsource (lib "eagle-import") (part "R-EU_0207/12"))
    )
    (comp (ref "R51")
      (value "4K7")
      (footprint "eagle-import:0207_12")
      (libsource (lib "eagle-import") (part "R-EU_0207/12"))
    )
    (comp (ref "R53")
      (value "47K")
      (footprint "eagle-import:0207_12")
      (libsource (lib "eagle-import") (part "R-EU_0207/12"))
    )
    (comp (ref "R54")
      (value "39K")
      (footprint "eagle-import:0207_12")
      (libsource (lib "eagle-import") (part "R-EU_0207/12"))
    )
    (comp (ref "R55")
      (value "1K")
      (footprint "eagle-import:0207_5V")
      (libsource (lib "eagle-import") (part "R-EU_0207/5V"))
    )
    (comp (ref "R56")
      (value "1K")
      (footprint "eagle-import:0207_5V")
      (libsource (lib "eagle-import") (part "R-EU_0207/5V"))
    )
    (comp (ref "R57")
      (value "220")
      (footprint "eagle-import:0207_5V")
      (libsource (lib "eagle-import") (part "R-EU_0207/5V"))
    )
    (comp (ref "R58")
      (value "220")
      (footprint "eagle-import:0207_5V")
      (libsource (lib "eagle-import") (part "R-EU_0207/5V"))
    )
    (comp (ref "R59")
      (value "470")
      (footprint "eagle-import:0207_5V")
      (libsource (lib "eagle-import") (part "R-EU_0207/5V"))
    )
    (comp (ref "R63")
      (value "4K7")
      (footprint "eagle-import:0207_12")
      (libsource (lib "eagle-import") (part "R-EU_0207/12"))
    )
    (comp (ref "R64")
      (value "4K7")
      (footprint "eagle-import:0207_12")
      (libsource (lib "eagle-import") (part "R-EU_0207/12"))
    )
    (comp (ref "R65")
      (value "1K")
      (footprint "eagle-import:0207_12")
      (libsource (lib "eagle-import") (part "R-EU_0207/12"))
    )
    (comp (ref "R66")
      (value "470")
      (footprint "eagle-import:0207_12")
      (libsource (lib "eagle-import") (part "R-EU_0207/12"))
    )
    (comp (ref "R67")
      (value "470")
      (footprint "eagle-import:0207_12")
      (libsource (lib "eagle-import") (part "R-EU_0207/12"))
    )
    (comp (ref "R68")
      (value "33")
      (footprint "eagle-import:0207_12")
      (libsource (lib "eagle-import") (part "R-EU_0207/12"))
    )
    (comp (ref "R69")
      (value "100")
      (footprint "eagle-import:0207_5V")
      (libsource (lib "eagle-import") (part "R-EU_0207/5V"))
    )
    (comp (ref "R70")
      (value "100")
      (footprint "eagle-import:0207_5V")
      (libsource (lib "eagle-import") (part "R-EU_0207/5V"))
    )
    (comp (ref "R71")
      (value "3K3")
      (footprint "eagle-import:0207_5V")
      (libsource (lib "eagle-import") (part "R-EU_0207/5V"))
    )
    (comp (ref "R72")
      (value "10K")
      (footprint "eagle-import:0207_5V")
      (libsource (lib "eagle-import") (part "R-EU_0207/5V"))
    )
    (comp (ref "R73")
      (value "10K")
      (footprint "eagle-import:0207_5V")
      (libsource (lib "eagle-import") (part "R-EU_0207/5V"))
    )
    (comp (ref "R73_")
      (value "3K3")
      (footprint "eagle-import:0207_12")
      (libsource (lib "eagle-import") (part "R-EU_0207/12"))
    )
    (comp (ref "R74")
      (value "10K")
      (footprint "eagle-import:0207_5V")
      (libsource (lib "eagle-import") (part "R-EU_0207/5V"))
    )
    (comp (ref "R74_")
      (value "470")
      (footprint "eagle-import:0207_12")
      (libsource (lib "eagle-import") (part "R-EU_0207/12"))
    )
    (comp (ref "R75")
      (value "10K")
      (footprint "eagle-import:0207_12")
      (libsource (lib "eagle-import") (part "R-EU_0207/12"))
    )
    (comp (ref "R76")
      (value "150")
      (footprint "eagle-import:0207_5V")
      (libsource (lib "eagle-import") (part "R-EU_0207/5V"))
    )
    (comp (ref "R77")
      (value "75")
      (footprint "eagle-import:0207_5V")
      (libsource (lib "eagle-import") (part "R-EU_0207/5V"))
    )
    (comp (ref "TP1")
      (value "TPSQPAD1-13")
      (footprint "eagle-import:P1-13")
      (libsource (lib "eagle-import") (part "TPSQPAD1-13"))
    )
    (comp (ref "TP2")
      (value "TPSQPAD1-13")
      (footprint "eagle-import:P1-13")
      (libsource (lib "eagle-import") (part "TPSQPAD1-13"))
    )
    (comp (ref "TP3")
      (value "TPSQPAD1-13")
      (footprint "eagle-import:P1-13")
      (libsource (lib "eagle-import") (part "TPSQPAD1-13"))
    )
    (comp (ref "TP4")
      (value "TPSQPAD1-13")
      (footprint "eagle-import:P1-13")
      (libsource (lib "eagle-import") (part "TPSQPAD1-13"))
    )
    (comp (ref "TP5")
      (value "TPSQPAD1-13")
      (footprint "eagle-import:P1-13")
      (libsource (lib "eagle-import") (part "TPSQPAD1-13"))
    )
    (comp (ref "TP6")
      (value "TPSQPAD1-13")
      (footprint "eagle-import:P1-13")
      (libsource (lib "eagle-import") (part "TPSQPAD1-13"))
    )
    (comp (ref "TP7")
      (value "TPSQPAD1-13")
      (footprint "eagle-import:P1-13")
      (libsource (lib "eagle-import") (part "TPSQPAD1-13"))
    )
    (comp (ref "TP8")
      (value "TPSQPAD1-13")
      (footprint "eagle-import:P1-13")
      (libsource (lib "eagle-import") (part "TPSQPAD1-13"))
    )
    (comp (ref "TP9")
      (value "TPSQPAD1-13")
      (footprint "eagle-import:P1-13")
      (libsource (lib "eagle-import") (part "TPSQPAD1-13"))
    )
    (comp (ref "TP10")
      (value "TPSQPAD1-13")
      (footprint "eagle-import:P1-13")
      (libsource (lib "eagle-import") (part "TPSQPAD1-13"))
    )
    (comp (ref "U$1")
      (value "TK90_EDGE")
      (footprint "eagle-import:TK-EDGE")
      (libsource (lib "eagle-import") (part "TK90_EDGE"))
    )
    (comp (ref "X1")
      (value "RCA2PINN1")
      (footprint "eagle-import:DX1")
      (libsource (lib "eagle-import") (part "RCA2PINN1"))
    )
    (comp (ref "X2")
      (value "POWER")
      (footprint "eagle-import:MONO")
      (libsource (lib "eagle-import") (part "JACK?-MONO"))
    )
    (comp (ref "XTAL")
      (value "14.3044MHz")
      (footprint "eagle-import:HC49_S")
      (libsource (lib "eagle-import") (part "CRYSTALHC49S"))
    )
  )
  (nets
    (net (code "1") (name "+5V") (class "Default")
      (node (ref "7805") (pin "OUT") (pinfunction "OUT_OUT") (pintype "passive"))
      (node (ref "C1") (pin "+") (pinfunction "+_+") (pintype "passive"))
      (node (ref "C12") (pin "2") (pinfunction "2_2") (pintype "passive"))
      (node (ref "C13") (pin "2") (pinfunction "2_2") (pintype "passive"))
      (node (ref "C14") (pin "2") (pinfunction "2_2") (pintype "passive"))
      (node (ref "C15") (pin "1") (pinfunction "1_1") (pintype "passive"))
      (node (ref "C16") (pin "1") (pinfunction "1_1") (pintype "passive"))
      (node (ref "C18") (pin "1") (pinfunction "1_1") (pintype "passive"))
      (node (ref "C19") (pin "1") (pinfunction "1_1") (pintype "passive"))
      (node (ref "C20") (pin "1") (pinfunction "1_1") (pintype "passive"))
      (node (ref "C21") (pin "1") (pinfunction "1_1") (pintype "passive"))
      (node (ref "C22") (pin "2") (pinfunction "2_2") (pintype "passive"))
      (node (ref "C24") (pin "2") (pinfunction "2_2") (pintype "passive"))
      (node (ref "C29") (pin "2") (pinfunction "2_2") (pintype "passive"))
      (node (ref "C31") (pin "2") (pinfunction "2_2") (pintype "passive"))
      (node (ref "C32") (pin "2") (pinfunction "2_2") (pintype "passive"))
      (node (ref "C33") (pin "2") (pinfunction "2_2") (pintype "passive"))
      (node (ref "D13") (pin "C") (pinfunction "K_C") (pintype "bidirectional"))
      (node (ref "D15") (pin "C") (pinfunction "K_C") (pintype "bidirectional"))
      (node (ref "D17") (pin "C") (pinfunction "K_C") (pintype "bidirectional"))
      (node (ref "IC1") (pin "11") (pinfunction "VCC_11") (pintype "power_in"))
      (node (ref "IC10") (pin "13") (pinfunction "A2_13") (pintype "input"))
      (node (ref "IC10") (pin "17") (pinfunction "A4_17") (pintype "input"))
      (node (ref "IC10") (pin "20") (pinfunction "VCC_20") (pintype "power_in"))
      (node (ref "IC11") (pin "20") (pinfunction "VCC_20") (pintype "power_in"))
      (node (ref "IC12") (pin "3") (pinfunction "CR_BIAS_3") (pintype "input"))
      (node (ref "IC13") (pin "9") (pinfunction "A7_9") (pintype "input"))
      (node (ref "IC14") (pin "9") (pinfunction "A7_9") (pintype "input"))
      (node (ref "IC15") (pin "9") (pinfunction "A7_9") (pintype "input"))
      (node (ref "IC16") (pin "9") (pinfunction "A7_9") (pintype "input"))
      (node (ref "IC17") (pin "9") (pinfunction "A7_9") (pintype "input"))
      (node (ref "IC18") (pin "9") (pinfunction "A7_9") (pintype "input"))
      (node (ref "IC19") (pin "9") (pinfunction "A7_9") (pintype "input"))
      (node (ref "IC2") (pin "1") (pinfunction "VPP_1") (pintype "input"))
      (node (ref "IC2") (pin "28") (pinfunction "VCC_28") (pintype "power_in"))
      (node (ref "IC20") (pin "9") (pinfunction "A7_9") (pintype "input"))
      (node (ref "IC21") (pin "9") (pinfunction "VCC_9") (pintype "power_in"))
      (node (ref "IC22") (pin "9") (pinfunction "VCC_9") (pintype "power_in"))
      (node (ref "IC23") (pin "9") (pinfunction "VCC_9") (pintype "power_in"))
      (node (ref "IC24") (pin "9") (pinfunction "VCC_9") (pintype "power_in"))
      (node (ref "IC25") (pin "14") (pinfunction "VCC_14") (pintype "power_in"))
      (node (ref "IC26") (pin "1") (pinfunction "I0_1") (pintype "input"))
      (node (ref "IC26") (pin "14") (pinfunction "VCC_14") (pintype "power_in"))
      (node (ref "IC27") (pin "14") (pinfunction "VCC_14") (pintype "power_in"))
      (node (ref "IC28") (pin "14") (pinfunction "VCC_14") (pintype "power_in"))
      (node (ref "IC3") (pin "40") (pinfunction "VCC_40") (pintype "power_in"))
      (node (ref "IC4") (pin "10") (pinfunction "PRE_10") (pintype "input"))
      (node (ref "IC4") (pin "13") (pinfunction "CLR_13") (pintype "input"))
      (node (ref "IC4") (pin "14") (pinfunction "VCC_14") (pintype "power_in"))
      (node (ref "IC5") (pin "1") (pinfunction "CLR_1") (pintype "input"))
      (node (ref "IC5") (pin "10") (pinfunction "PRE_10") (pintype "input"))
      (node (ref "IC5") (pin "13") (pinfunction "CLR_13") (pintype "input"))
      (node (ref "IC5") (pin "14") (pinfunction "VCC_14") (pintype "power_in"))
      (node (ref "IC5") (pin "4") (pinfunction "PRE_4") (pintype "input"))
      (node (ref "IC6") (pin "16") (pinfunction "VCC_16") (pintype "power_in"))
      (node (ref "IC7") (pin "16") (pinfunction "VCC_16") (pintype "power_in"))
      (node (ref "IC8") (pin "16") (pinfunction "VCC_16") (pintype "power_in"))
      (node (ref "IC9") (pin "16") (pinfunction "VCC_16") (pintype "power_in"))
      (node (ref "J1") (pin "1") (pinfunction "1_1") (pintype "passive"))
      (node (ref "J2") (pin "1") (pinfunction "1_1") (pintype "passive"))
      (node (ref "Q1") (pin "3") (pinfunction "C_3") (pintype "passive"))
      (node (ref "R17") (pin "2") (pinfunction "2_2") (pintype "passive"))
      (node (ref "R18") (pin "2") (pinfunction "2_2") (pintype "passive"))
      (node (ref "R19") (pin "2") (pinfunction "2_2") (pintype "passive"))
      (node (ref "R20") (pin "2") (pinfunction "2_2") (pintype "passive"))
      (node (ref "R21") (pin "2") (pinfunction "2_2") (pintype "passive"))
      (node (ref "R22") (pin "2") (pinfunction "2_2") (pintype "passive"))
      (node (ref "R23") (pin "2") (pinfunction "2_2") (pintype "passive"))
      (node (ref "R24") (pin "2") (pinfunction "2_2") (pintype "passive"))
      (node (ref "R29") (pin "2") (pinfunction "2_2") (pintype "passive"))
      (node (ref "R30") (pin "1") (pinfunction "1_1") (pintype "passive"))
      (node (ref "R31") (pin "1") (pinfunction "1_1") (pintype "passive"))
      (node (ref "R32") (pin "1") (pinfunction "1_1") (pintype "passive"))
      (node (ref "R35") (pin "1") (pinfunction "1_1") (pintype "passive"))
      (node (ref "R36") (pin "1") (pinfunction "1_1") (pintype "passive"))
      (node (ref "R37") (pin "1") (pinfunction "1_1") (pintype "passive"))
      (node (ref "R38") (pin "1") (pinfunction "1_1") (pintype "passive"))
      (node (ref "R39") (pin "1") (pinfunction "1_1") (pintype "passive"))
      (node (ref "R40") (pin "2") (pinfunction "2_2") (pintype "passive"))
      (node (ref "R43") (pin "2") (pinfunction "2_2") (pintype "passive"))
      (node (ref "R48") (pin "2") (pinfunction "2_2") (pintype "passive"))
      (node (ref "R51") (pin "2") (pinfunction "2_2") (pintype "passive"))
      (node (ref "R74_") (pin "2") (pinfunction "2_2") (pintype "passive"))
      (node (ref "U$1") (pin "3A") (pinfunction "EDGE_3A") (pintype "bidirectional"))
    )
    (net (code "2") (name "+12V") (class "Default")
      (node (ref "C43") (pin "2") (pinfunction "2_2") (pintype "passive"))
      (node (ref "C53") (pin "+") (pinfunction "+_+") (pintype "passive"))
      (node (ref "D24") (pin "C") (pinfunction "K_C") (pintype "bidirectional"))
      (node (ref "IC11") (pin "5") (pinfunction "+12V_5") (pintype "power_in"))
      (node (ref "IC12") (pin "14") (pinfunction "RFVCC_14") (pintype "power_in"))
      (node (ref "IC12") (pin "16") (pinfunction "CRVCC_16") (pintype "power_in"))
      (node (ref "L1") (pin "2") (pinfunction "A_2") (pintype "passive"))
      (node (ref "Q8") (pin "3") (pinfunction "C_3") (pintype "passive"))
      (node (ref "R54") (pin "1") (pinfunction "1_1") (pintype "passive"))
      (node (ref "R57") (pin "1") (pinfunction "1_1") (pintype "passive"))
      (node (ref "R58") (pin "1") (pinfunction "1_1") (pintype "passive"))
      (node (ref "R59") (pin "1") (pinfunction "1_1") (pintype "passive"))
      (node (ref "R68") (pin "1") (pinfunction "1_1") (pintype "passive"))
      (node (ref "U$1") (pin "22B") (pinfunction "EDGE_22B") (pintype "bidirectional"))
    )
    (net (code "3") (name "-5V") (class "Default")
      (node (ref "C50") (pin "1") (pinfunction "1_1") (pintype "passive"))
      (node (ref "D21") (pin "A") (pinfunction "A_A") (pintype "bidirectional"))
      (node (ref "J3") (pin "1") (pinfunction "1_1") (pintype "passive"))
      (node (ref "R67") (pin "1") (pinfunction "1_1") (pintype "passive"))
      (node (ref "U$1") (pin "20B") (pinfunction "EDGE_20B") (pintype "bidirectional"))
    )
    (net (code "4") (name "/+12V_UNREG") (class "Default")
      (node (ref "C48") (pin "1") (pinfunction "1_1") (pintype "passive"))
      (node (ref "C51") (pin "1") (pinfunction "1_1") (pintype "passive"))
      (node (ref "Q5") (pin "E") (pinfunction "E_E") (pintype "passive"))
      (node (ref "Q6") (pin "E") (pinfunction "E_E") (pintype "passive"))
      (node (ref "U$1") (pin "23B") (pinfunction "EDGE_23B") (pintype "bidirectional"))
    )
    (net (code "5") (name "/A0") (class "Default")
      (node (ref "IC1") (pin "30") (pinfunction "A0_30") (pintype "output"))
      (node (ref "IC2") (pin "10") (pinfunction "A0_10") (pintype "input"))
      (node (ref "IC7") (pin "3") (pinfunction "1B_3") (pintype "input"))
      (node (ref "IC8") (pin "3") (pinfunction "1B_3") (pintype "input"))
      (node (ref "Q1") (pin "2") (pinfunction "B_2") (pintype "passive"))
      (node (ref "U$1") (pin "9A") (pinfunction "EDGE_9A") (pintype "bidirectional"))
    )
    (net (code "6") (name "/A1") (class "Default")
      (node (ref "IC1") (pin "31") (pinfunction "A1_31") (pintype "output"))
      (node (ref "IC2") (pin "9") (pinfunction "A1_9") (pintype "input"))
      (node (ref "IC7") (pin "6") (pinfunction "2B_6") (pintype "input"))
      (node (ref "IC8") (pin "6") (pinfunction "2B_6") (pintype "input"))
      (node (ref "U$1") (pin "10A") (pinfunction "EDGE_10A") (pintype "bidirectional"))
    )
    (net (code "7") (name "/A2") (class "Default")
      (node (ref "IC1") (pin "32") (pinfunction "A2_32") (pintype "output"))
      (node (ref "IC2") (pin "8") (pinfunction "A2_8") (pintype "input"))
      (node (ref "IC7") (pin "13") (pinfunction "4B_13") (pintype "input"))
      (node (ref "IC8") (pin "13") (pinfunction "4B_13") (pintype "input"))
      (node (ref "U$1") (pin "11A") (pinfunction "EDGE_11A") (pintype "bidirectional"))
    )
    (net (code "8") (name "/A3") (class "Default")
      (node (ref "IC1") (pin "33") (pinfunction "A3_33") (pintype "output"))
      (node (ref "IC2") (pin "7") (pinfunction "A3_7") (pintype "input"))
      (node (ref "IC7") (pin "10") (pinfunction "3B_10") (pintype "input"))
      (node (ref "IC8") (pin "10") (pinfunction "3B_10") (pintype "input"))
      (node (ref "U$1") (pin "12A") (pinfunction "EDGE_12A") (pintype "bidirectional"))
    )
    (net (code "9") (name "/A4") (class "Default")
      (node (ref "IC1") (pin "34") (pinfunction "A4_34") (pintype "output"))
      (node (ref "IC2") (pin "6") (pinfunction "A4_6") (pintype "input"))
      (node (ref "IC6") (pin "6") (pinfunction "2B_6") (pintype "input"))
      (node (ref "IC9") (pin "6") (pinfunction "2B_6") (pintype "input"))
      (node (ref "U$1") (pin "24A") (pinfunction "EDGE_24A") (pintype "bidirectional"))
    )
    (net (code "10") (name "/A5") (class "Default")
      (node (ref "IC1") (pin "35") (pinfunction "A5_35") (pintype "output"))
      (node (ref "IC2") (pin "5") (pinfunction "A5_5") (pintype "input"))
      (node (ref "IC6") (pin "13") (pinfunction "4B_13") (pintype "input"))
      (node (ref "IC9") (pin "13") (pinfunction "4B_13") (pintype "input"))
      (node (ref "U$1") (pin "23A") (pinfunction "EDGE_23A") (pintype "bidirectional"))
    )
    (net (code "11") (name "/A6") (class "Default")
      (node (ref "IC1") (pin "36") (pinfunction "A6_36") (pintype "output"))
      (node (ref "IC2") (pin "4") (pinfunction "A6_4") (pintype "input"))
      (node (ref "IC21") (pin "14") (pinfunction "A0_14") (pintype "input"))
      (node (ref "IC22") (pin "14") (pinfunction "A0_14") (pintype "input"))
      (node (ref "IC23") (pin "14") (pinfunction "A0_14") (pintype "input"))
      (node (ref "IC24") (pin "14") (pinfunction "A0_14") (pintype "input"))
      (node (ref "IC5") (pin "12") (pinfunction "D_12") (pintype "input"))
      (node (ref "IC9") (pin "10") (pinfunction "3B_10") (pintype "input"))
      (node (ref "U$1") (pin "22A") (pinfunction "EDGE_22A") (pintype "bidirectional"))
    )
    (net (code "12") (name "/A7") (class "Default")
      (node (ref "IC1") (pin "37") (pinfunction "A7_37") (pintype "output"))
      (node (ref "IC2") (pin "3") (pinfunction "A7_3") (pintype "input"))
      (node (ref "IC26") (pin "12") (pinfunction "I0_12") (pintype "input"))
      (node (ref "IC8") (pin "2") (pinfunction "1A_2") (pintype "input"))
      (node (ref "U$1") (pin "21A") (pinfunction "EDGE_21A") (pintype "bidirectional"))
    )
    (net (code "13") (name "/A7'") (class "Default")
      (node (ref "IC21") (pin "10") (pinfunction "A7_10") (pintype "input"))
      (node (ref "IC22") (pin "10") (pinfunction "A7_10") (pintype "input"))
      (node (ref "IC23") (pin "10") (pinfunction "A7_10") (pintype "input"))
      (node (ref "IC24") (pin "10") (pinfunction "A7_10") (pintype "input"))
      (node (ref "IC26") (pin "8") (pinfunction "O_8") (pintype "output"))
    )
    (net (code "14") (name "/A8") (class "Default")
      (node (ref "D2") (pin "C") (pinfunction "K_C") (pintype "bidirectional"))
      (node (ref "IC1") (pin "38") (pinfunction "A8_38") (pintype "output"))
      (node (ref "IC2") (pin "25") (pinfunction "A8_25") (pintype "input"))
      (node (ref "IC7") (pin "5") (pinfunction "2A_5") (pintype "input"))
      (node (ref "IC8") (pin "5") (pinfunction "2A_5") (pintype "input"))
      (node (ref "U$1") (pin "26B") (pinfunction "EDGE_26B") (pintype "bidirectional"))
    )
    (net (code "15") (name "/A8-1") (class "Default")
      (node (ref "IC21") (pin "7") (pinfunction "A5_7") (pintype "input"))
      (node (ref "IC22") (pin "7") (pinfunction "A5_7") (pintype "input"))
      (node (ref "IC23") (pin "7") (pinfunction "A5_7") (pintype "input"))
      (node (ref "IC24") (pin "7") (pinfunction "A5_7") (pintype "input"))
      (node (ref "IC7") (pin "7") (pinfunction "2Y_7") (pintype "output"))
    )
    (net (code "16") (name "/A9") (class "Default")
      (node (ref "D3") (pin "C") (pinfunction "K_C") (pintype "bidirectional"))
      (node (ref "IC1") (pin "39") (pinfunction "A9_39") (pintype "output"))
      (node (ref "IC2") (pin "24") (pinfunction "A9_24") (pintype "input"))
      (node (ref "IC7") (pin "14") (pinfunction "4A_14") (pintype "input"))
      (node (ref "IC8") (pin "14") (pinfunction "4A_14") (pintype "input"))
      (node (ref "U$1") (pin "27A") (pinfunction "EDGE_27A") (pintype "bidirectional"))
    )
    (net (code "17") (name "/A9-2") (class "Default")
      (node (ref "IC21") (pin "8") (pinfunction "A4_8") (pintype "input"))
      (node (ref "IC22") (pin "8") (pinfunction "A4_8") (pintype "input"))
      (node (ref "IC23") (pin "8") (pinfunction "A4_8") (pintype "input"))
      (node (ref "IC24") (pin "8") (pinfunction "A4_8") (pintype "input"))
      (node (ref "IC7") (pin "12") (pinfunction "4Y_12") (pintype "output"))
    )
    (net (code "18") (name "/A10") (class "Default")
      (node (ref "D4") (pin "C") (pinfunction "K_C") (pintype "bidirectional"))
      (node (ref "IC1") (pin "40") (pinfunction "A10_40") (pintype "output"))
      (node (ref "IC2") (pin "21") (pinfunction "A10_21") (pintype "input"))
      (node (ref "IC7") (pin "11") (pinfunction "3A_11") (pintype "input"))
      (node (ref "IC8") (pin "11") (pinfunction "3A_11") (pintype "input"))
      (node (ref "U$1") (pin "27B") (pinfunction "EDGE_27B") (pintype "bidirectional"))
    )
    (net (code "19") (name "/A10-3") (class "Default")
      (node (ref "IC21") (pin "11") (pinfunction "A3_11") (pintype "input"))
      (node (ref "IC22") (pin "11") (pinfunction "A3_11") (pintype "input"))
      (node (ref "IC23") (pin "11") (pinfunction "A3_11") (pintype "input"))
      (node (ref "IC24") (pin "11") (pinfunction "A3_11") (pintype "input"))
      (node (ref "IC7") (pin "9") (pinfunction "3Y_9") (pintype "output"))
    )
    (net (code "20") (name "/A11") (class "Default")
      (node (ref "D5") (pin "C") (pinfunction "K_C") (pintype "bidirectional"))
      (node (ref "IC1") (pin "1") (pinfunction "A11_1") (pintype "output"))
      (node (ref "IC2") (pin "23") (pinfunction "A11_23") (pintype "input"))
      (node (ref "IC6") (pin "5") (pinfunction "2A_5") (pintype "input"))
      (node (ref "IC9") (pin "5") (pinfunction "2A_5") (pintype "input"))
      (node (ref "U$1") (pin "28A") (pinfunction "EDGE_28A") (pintype "bidirectional"))
    )
    (net (code "21") (name "/A11-4") (class "Default")
      (node (ref "IC21") (pin "12") (pinfunction "A2_12") (pintype "input"))
      (node (ref "IC22") (pin "12") (pinfunction "A2_12") (pintype "input"))
      (node (ref "IC23") (pin "12") (pinfunction "A2_12") (pintype "input"))
      (node (ref "IC24") (pin "12") (pinfunction "A2_12") (pintype "input"))
      (node (ref "IC6") (pin "7") (pinfunction "2Y_7") (pintype "output"))
    )
    (net (code "22") (name "/A12") (class "Default")
      (node (ref "D6") (pin "C") (pinfunction "K_C") (pintype "bidirectional"))
      (node (ref "IC1") (pin "2") (pinfunction "A12_2") (pintype "output"))
      (node (ref "IC2") (pin "2") (pinfunction "A12_2") (pintype "input"))
      (node (ref "IC6") (pin "14") (pinfunction "4A_14") (pintype "input"))
      (node (ref "IC9") (pin "14") (pinfunction "4A_14") (pintype "input"))
      (node (ref "U$1") (pin "2A") (pinfunction "EDGE_2A") (pintype "bidirectional"))
    )
    (net (code "23") (name "/A12-5") (class "Default")
      (node (ref "IC21") (pin "13") (pinfunction "A1_13") (pintype "input"))
      (node (ref "IC22") (pin "13") (pinfunction "A1_13") (pintype "input"))
      (node (ref "IC23") (pin "13") (pinfunction "A1_13") (pintype "input"))
      (node (ref "IC24") (pin "13") (pinfunction "A1_13") (pintype "input"))
      (node (ref "IC6") (pin "12") (pinfunction "4Y_12") (pintype "output"))
    )
    (net (code "24") (name "/A13") (class "Default")
      (node (ref "D7") (pin "C") (pinfunction "K_C") (pintype "bidirectional"))
      (node (ref "IC1") (pin "3") (pinfunction "A13_3") (pintype "output"))
      (node (ref "IC2") (pin "26") (pinfunction "A13_26") (pintype "input"))
      (node (ref "IC7") (pin "2") (pinfunction "1A_2") (pintype "input"))
      (node (ref "IC9") (pin "11") (pinfunction "3A_11") (pintype "input"))
      (node (ref "U$1") (pin "2B") (pinfunction "EDGE_2B") (pintype "bidirectional"))
    )
    (net (code "25") (name "/A13-0") (class "Default")
      (node (ref "IC21") (pin "6") (pinfunction "A6_6") (pintype "input"))
      (node (ref "IC22") (pin "6") (pinfunction "A6_6") (pintype "input"))
      (node (ref "IC23") (pin "6") (pinfunction "A6_6") (pintype "input"))
      (node (ref "IC24") (pin "6") (pinfunction "A6_6") (pintype "input"))
      (node (ref "IC7") (pin "4") (pinfunction "1Y_4") (pintype "output"))
    )
    (net (code "26") (name "/A14") (class "Default")
      (node (ref "D12") (pin "A") (pinfunction "A_A") (pintype "bidirectional"))
      (node (ref "D8") (pin "C") (pinfunction "K_C") (pintype "bidirectional"))
      (node (ref "IC1") (pin "4") (pinfunction "A14_4") (pintype "output"))
      (node (ref "IC25") (pin "4") (pinfunction "I0_4") (pintype "input"))
      (node (ref "IC27") (pin "12") (pinfunction "I0_12") (pintype "input"))
      (node (ref "IC28") (pin "1") (pinfunction "I_1") (pintype "input"))
      (node (ref "IC3") (pin "37") (pinfunction "A14_37") (pintype "input"))
      (node (ref "U$1") (pin "1A") (pinfunction "EDGE_1A") (pintype "bidirectional"))
    )
    (net (code "27") (name "/A15") (class "Default")
      (node (ref "D11") (pin "A") (pinfunction "A_A") (pintype "bidirectional"))
      (node (ref "D9") (pin "C") (pinfunction "K_C") (pintype "bidirectional"))
      (node (ref "IC1") (pin "5") (pinfunction "A15_5") (pintype "output"))
      (node (ref "IC25") (pin "13") (pinfunction "I1_13") (pintype "input"))
      (node (ref "IC27") (pin "13") (pinfunction "I1_13") (pintype "input"))
      (node (ref "IC3") (pin "38") (pinfunction "A15_38") (pintype "input"))
      (node (ref "U$1") (pin "1B") (pinfunction "EDGE_1B") (pintype "bidirectional"))
    )
    (net (code "28") (name "/AA0") (class "Default")
      (node (ref "IC13") (pin "5") (pinfunction "A0_5") (pintype "input"))
      (node (ref "IC14") (pin "5") (pinfunction "A0_5") (pintype "input"))
      (node (ref "IC15") (pin "5") (pinfunction "A0_5") (pintype "input"))
      (node (ref "IC16") (pin "5") (pinfunction "A0_5") (pintype "input"))
      (node (ref "IC17") (pin "5") (pinfunction "A0_5") (pintype "input"))
      (node (ref "IC18") (pin "5") (pinfunction "A0_5") (pintype "input"))
      (node (ref "IC19") (pin "5") (pinfunction "A0_5") (pintype "input"))
      (node (ref "IC20") (pin "5") (pinfunction "A0_5") (pintype "input"))
      (node (ref "IC3") (pin "9") (pinfunction "A0_9") (pintype "output"))
      (node (ref "R9") (pin "1") (pinfunction "1_1") (pintype "passive"))
    )
    (net (code "29") (name "/AA1") (class "Default")
      (node (ref "IC13") (pin "7") (pinfunction "A1_7") (pintype "input"))
      (node (ref "IC14") (pin "7") (pinfunction "A1_7") (pintype "input"))
      (node (ref "IC15") (pin "7") (pinfunction "A1_7") (pintype "input"))
      (node (ref "IC16") (pin "7") (pinfunction "A1_7") (pintype "input"))
      (node (ref "IC17") (pin "7") (pinfunction "A1_7") (pintype "input"))
      (node (ref "IC18") (pin "7") (pinfunction "A1_7") (pintype "input"))
      (node (ref "IC19") (pin "7") (pinfunction "A1_7") (pintype "input"))
      (node (ref "IC20") (pin "7") (pinfunction "A1_7") (pintype "input"))
      (node (ref "IC3") (pin "7") (pinfunction "A1_7") (pintype "output"))
      (node (ref "R11") (pin "1") (pinfunction "1_1") (pintype "passive"))
    )
    (net (code "30") (name "/AA2") (class "Default")
      (node (ref "IC13") (pin "6") (pinfunction "A2_6") (pintype "input"))
      (node (ref "IC14") (pin "6") (pinfunction "A2_6") (pintype "input"))
      (node (ref "IC15") (pin "6") (pinfunction "A2_6") (pintype "input"))
      (node (ref "IC16") (pin "6") (pinfunction "A2_6") (pintype "input"))
      (node (ref "IC17") (pin "6") (pinfunction "A2_6") (pintype "input"))
      (node (ref "IC18") (pin "6") (pinfunction "A2_6") (pintype "input"))
      (node (ref "IC19") (pin "6") (pinfunction "A2_6") (pintype "input"))
      (node (ref "IC20") (pin "6") (pinfunction "A2_6") (pintype "input"))
      (node (ref "IC3") (pin "8") (pinfunction "A2_8") (pintype "output"))
      (node (ref "R10") (pin "1") (pinfunction "1_1") (pintype "passive"))
    )
    (net (code "31") (name "/AA3") (class "Default")
      (node (ref "IC13") (pin "12") (pinfunction "A3_12") (pintype "input"))
      (node (ref "IC14") (pin "12") (pinfunction "A3_12") (pintype "input"))
      (node (ref "IC15") (pin "12") (pinfunction "A3_12") (pintype "input"))
      (node (ref "IC16") (pin "12") (pinfunction "A3_12") (pintype "input"))
      (node (ref "IC17") (pin "12") (pinfunction "A3_12") (pintype "input"))
      (node (ref "IC18") (pin "12") (pinfunction "A3_12") (pintype "input"))
      (node (ref "IC19") (pin "12") (pinfunction "A3_12") (pintype "input"))
      (node (ref "IC20") (pin "12") (pinfunction "A3_12") (pintype "input"))
      (node (ref "IC3") (pin "4") (pinfunction "A3_4") (pintype "output"))
      (node (ref "R14") (pin "1") (pinfunction "1_1") (pintype "passive"))
    )
    (net (code "32") (name "/AA4") (class "Default")
      (node (ref "IC13") (pin "11") (pinfunction "A4_11") (pintype "input"))
      (node (ref "IC14") (pin "11") (pinfunction "A4_11") (pintype "input"))
      (node (ref "IC15") (pin "11") (pinfunction "A4_11") (pintype "input"))
      (node (ref "IC16") (pin "11") (pinfunction "A4_11") (pintype "input"))
      (node (ref "IC17") (pin "11") (pinfunction "A4_11") (pintype "input"))
      (node (ref "IC18") (pin "11") (pinfunction "A4_11") (pintype "input"))
      (node (ref "IC19") (pin "11") (pinfunction "A4_11") (pintype "input"))
      (node (ref "IC20") (pin "11") (pinfunction "A4_11") (pintype "input"))
      (node (ref "IC3") (pin "5") (pinfunction "A4_5") (pintype "output"))
      (node (ref "R13") (pin "1") (pinfunction "1_1") (pintype "passive"))
    )
    (net (code "33") (name "/AA5") (class "Default")
      (node (ref "IC13") (pin "10") (pinfunction "A5_10") (pintype "input"))
      (node (ref "IC14") (pin "10") (pinfunction "A5_10") (pintype "input"))
      (node (ref "IC15") (pin "10") (pinfunction "A5_10") (pintype "input"))
      (node (ref "IC16") (pin "10") (pinfunction "A5_10") (pintype "input"))
      (node (ref "IC17") (pin "10") (pinfunction "A5_10") (pintype "input"))
      (node (ref "IC18") (pin "10") (pinfunction "A5_10") (pintype "input"))
      (node (ref "IC19") (pin "10") (pinfunction "A5_10") (pintype "input"))
      (node (ref "IC20") (pin "10") (pinfunction "A5_10") (pintype "input"))
      (node (ref "IC3") (pin "6") (pinfunction "A5_6") (pintype "output"))
      (node (ref "R12") (pin "1") (pinfunction "1_1") (pintype "passive"))
    )
    (net (code "34") (name "/AA6") (class "Default")
      (node (ref "IC13") (pin "13") (pinfunction "A6_13") (pintype "input"))
      (node (ref "IC14") (pin "13") (pinfunction "A6_13") (pintype "input"))
      (node (ref "IC15") (pin "13") (pinfunction "A6_13") (pintype "input"))
      (node (ref "IC16") (pin "13") (pinfunction "A6_13") (pintype "input"))
      (node (ref "IC17") (pin "13") (pinfunction "A6_13") (pintype "input"))
      (node (ref "IC18") (pin "13") (pinfunction "A6_13") (pintype "input"))
      (node (ref "IC19") (pin "13") (pinfunction "A6_13") (pintype "input"))
      (node (ref "IC20") (pin "13") (pinfunction "A6_13") (pintype "input"))
      (node (ref "IC3") (pin "3") (pinfunction "A6_3") (pintype "output"))
      (node (ref "R15") (pin "1") (pinfunction "1_1") (pintype "passive"))
    )
    (net (code "35") (name "/CARRIER") (class "Default")
      (node (ref "C47") (pin "1") (pinfunction "1_1") (pintype "passive"))
      (node (ref "D17") (pin "A") (pinfunction "A_A") (pintype "bidirectional"))
      (node (ref "D18") (pin "C") (pinfunction "K_C") (pintype "bidirectional"))
      (node (ref "IC3") (pin "39") (pinfunction "CARRIER_39") (pintype "output"))
      (node (ref "R64") (pin "2") (pinfunction "2_2") (pintype "passive"))
      (node (ref "R71") (pin "2") (pinfunction "2_2") (pintype "passive"))
    )
    (net (code "36") (name "/CLK") (class "Default")
      (node (ref "C9") (pin "2") (pinfunction "2_2") (pintype "passive"))
      (node (ref "IC3") (pin "36") (pinfunction "CKOUT_36") (pintype "output"))
      (node (ref "R49") (pin "2") (pinfunction "2_2") (pintype "passive"))
      (node (ref "R51") (pin "1") (pinfunction "1_1") (pintype "passive"))
      (node (ref "U$1") (pin "8A") (pinfunction "EDGE_8A") (pintype "bidirectional"))
    )
    (net (code "37") (name "/D0") (class "Default")
      (node (ref "IC1") (pin "14") (pinfunction "D0_14") (pintype "bidirectional"))
      (node (ref "IC10") (pin "18") (pinfunction "Y1_18") (pintype "tri_state"))
      (node (ref "IC2") (pin "11") (pinfunction "O0_11") (pintype "tri_state"))
      (node (ref "IC21") (pin "2") (pinfunction "I/O1_2") (pintype "bidirectional"))
      (node (ref "IC23") (pin "2") (pinfunction "I/O1_2") (pintype "bidirectional"))
      (node (ref "R1") (pin "2") (pinfunction "2_2") (pintype "passive"))
      (node (ref "R17") (pin "1") (pinfunction "1_1") (pintype "passive"))
      (node (ref "U$1") (pin "6B") (pinfunction "EDGE_6B") (pintype "bidirectional"))
    )
    (net (code "38") (name "/D0'") (class "Default")
      (node (ref "IC20") (pin "14") (pinfunction "DO_14") (pintype "bidirectional"))
      (node (ref "IC20") (pin "2") (pinfunction "DI_2") (pintype "bidirectional"))
      (node (ref "IC3") (pin "25") (pinfunction "D0_25") (pintype "bidirectional"))
      (node (ref "R1") (pin "1") (pinfunction "1_1") (pintype "passive"))
    )
    (net (code "39") (name "/D1") (class "Default")
      (node (ref "IC1") (pin "15") (pinfunction "D1_15") (pintype "bidirectional"))
      (node (ref "IC10") (pin "16") (pinfunction "Y2_16") (pintype "tri_state"))
      (node (ref "IC2") (pin "12") (pinfunction "O1_12") (pintype "tri_state"))
      (node (ref "IC21") (pin "3") (pinfunction "I/O2_3") (pintype "bidirectional"))
      (node (ref "IC23") (pin "3") (pinfunction "I/O2_3") (pintype "bidirectional"))
      (node (ref "R18") (pin "1") (pinfunction "1_1") (pintype "passive"))
      (node (ref "R2") (pin "2") (pinfunction "2_2") (pintype "passive"))
      (node (ref "U$1") (pin "7B") (pinfunction "EDGE_7B") (pintype "bidirectional"))
    )
    (net (code "40") (name "/D1'") (class "Default")
      (node (ref "IC19") (pin "14") (pinfunction "DO_14") (pintype "bidirectional"))
      (node (ref "IC19") (pin "2") (pinfunction "DI_2") (pintype "bidirectional"))
      (node (ref "IC3") (pin "26") (pinfunction "D1_26") (pintype "bidirectional"))
      (node (ref "R2") (pin "1") (pinfunction "1_1") (pintype "passive"))
    )
    (net (code "41") (name "/D2") (class "Default")
      (node (ref "IC1") (pin "12") (pinfunction "D2_12") (pintype "bidirectional"))
      (node (ref "IC10") (pin "14") (pinfunction "Y3_14") (pintype "tri_state"))
      (node (ref "IC2") (pin "13") (pinfunction "O2_13") (pintype "tri_state"))
      (node (ref "IC21") (pin "15") (pinfunction "I/O3_15") (pintype "bidirectional"))
      (node (ref "IC23") (pin "15") (pinfunction "I/O3_15") (pintype "bidirectional"))
      (node (ref "R19") (pin "1") (pinfunction "1_1") (pintype "passive"))
      (node (ref "R3") (pin "2") (pinfunction "2_2") (pintype "passive"))
      (node (ref "U$1") (pin "8B") (pinfunction "EDGE_8B") (pintype "bidirectional"))
    )
    (net (code "42") (name "/D2'") (class "Default")
      (node (ref "IC18") (pin "14") (pinfunction "DO_14") (pintype "bidirectional"))
      (node (ref "IC18") (pin "2") (pinfunction "DI_2") (pintype "bidirectional"))
      (node (ref "IC3") (pin "27") (pinfunction "D2_27") (pintype "bidirectional"))
      (node (ref "R3") (pin "1") (pinfunction "1_1") (pintype "passive"))
    )
    (net (code "43") (name "/D3") (class "Default")
      (node (ref "IC1") (pin "8") (pinfunction "D3_8") (pintype "bidirectional"))
      (node (ref "IC10") (pin "12") (pinfunction "Y4_12") (pintype "tri_state"))
      (node (ref "IC2") (pin "15") (pinfunction "O3_15") (pintype "tri_state"))
      (node (ref "IC21") (pin "17") (pinfunction "I/O4_17") (pintype "bidirectional"))
      (node (ref "IC23") (pin "17") (pinfunction "I/O4_17") (pintype "bidirectional"))
      (node (ref "R20") (pin "1") (pinfunction "1_1") (pintype "passive"))
      (node (ref "R4") (pin "2") (pinfunction "2_2") (pintype "passive"))
      (node (ref "U$1") (pin "11B") (pinfunction "EDGE_11B") (pintype "bidirectional"))
    )
    (net (code "44") (name "/D3'") (class "Default")
      (node (ref "IC17") (pin "14") (pinfunction "DO_14") (pintype "bidirectional"))
      (node (ref "IC17") (pin "2") (pinfunction "DI_2") (pintype "bidirectional"))
      (node (ref "IC3") (pin "28") (pinfunction "D3_28") (pintype "bidirectional"))
      (node (ref "R4") (pin "1") (pinfunction "1_1") (pintype "passive"))
    )
    (net (code "45") (name "/D4") (class "Default")
      (node (ref "IC1") (pin "7") (pinfunction "D4_7") (pintype "bidirectional"))
      (node (ref "IC10") (pin "9") (pinfunction "Y1_9") (pintype "tri_state"))
      (node (ref "IC2") (pin "16") (pinfunction "O4_16") (pintype "tri_state"))
      (node (ref "IC22") (pin "2") (pinfunction "I/O1_2") (pintype "bidirectional"))
      (node (ref "IC24") (pin "2") (pinfunction "I/O1_2") (pintype "bidirectional"))
      (node (ref "R21") (pin "1") (pinfunction "1_1") (pintype "passive"))
      (node (ref "R5") (pin "2") (pinfunction "2_2") (pintype "passive"))
      (node (ref "U$1") (pin "12B") (pinfunction "EDGE_12B") (pintype "bidirectional"))
    )
    (net (code "46") (name "/D4'") (class "Default")
      (node (ref "IC16") (pin "14") (pinfunction "DO_14") (pintype "bidirectional"))
      (node (ref "IC16") (pin "2") (pinfunction "DI_2") (pintype "bidirectional"))
      (node (ref "IC3") (pin "29") (pinfunction "D4_29") (pintype "bidirectional"))
      (node (ref "R5") (pin "1") (pinfunction "1_1") (pintype "passive"))
    )
    (net (code "47") (name "/D5") (class "Default")
      (node (ref "IC1") (pin "9") (pinfunction "D5_9") (pintype "bidirectional"))
      (node (ref "IC10") (pin "7") (pinfunction "Y2_7") (pintype "tri_state"))
      (node (ref "IC2") (pin "17") (pinfunction "O5_17") (pintype "tri_state"))
      (node (ref "IC22") (pin "3") (pinfunction "I/O2_3") (pintype "bidirectional"))
      (node (ref "IC24") (pin "3") (pinfunction "I/O2_3") (pintype "bidirectional"))
      (node (ref "R22") (pin "1") (pinfunction "1_1") (pintype "passive"))
      (node (ref "R6") (pin "2") (pinfunction "2_2") (pintype "passive"))
      (node (ref "U$1") (pin "10B") (pinfunction "EDGE_10B") (pintype "bidirectional"))
    )
    (net (code "48") (name "/D5'") (class "Default")
      (node (ref "IC15") (pin "14") (pinfunction "DO_14") (pintype "bidirectional"))
      (node (ref "IC15") (pin "2") (pinfunction "DI_2") (pintype "bidirectional"))
      (node (ref "IC3") (pin "30") (pinfunction "D5_30") (pintype "bidirectional"))
      (node (ref "R6") (pin "1") (pinfunction "1_1") (pintype "passive"))
    )
    (net (code "49") (name "/D6") (class "Default")
      (node (ref "IC1") (pin "10") (pinfunction "D6_10") (pintype "bidirectional"))
      (node (ref "IC10") (pin "5") (pinfunction "Y3_5") (pintype "tri_state"))
      (node (ref "IC2") (pin "18") (pinfunction "O6_18") (pintype "tri_state"))
      (node (ref "IC22") (pin "15") (pinfunction "I/O3_15") (pintype "bidirectional"))
      (node (ref "IC24") (pin "15") (pinfunction "I/O3_15") (pintype "bidirectional"))
      (node (ref "R23") (pin "1") (pinfunction "1_1") (pintype "passive"))
      (node (ref "R7") (pin "2") (pinfunction "2_2") (pintype "passive"))
      (node (ref "U$1") (pin "9B") (pinfunction "EDGE_9B") (pintype "bidirectional"))
    )
    (net (code "50") (name "/D6'") (class "Default")
      (node (ref "IC14") (pin "14") (pinfunction "DO_14") (pintype "bidirectional"))
      (node (ref "IC14") (pin "2") (pinfunction "DI_2") (pintype "bidirectional"))
      (node (ref "IC3") (pin "31") (pinfunction "D6_31") (pintype "bidirectional"))
      (node (ref "R7") (pin "1") (pinfunction "1_1") (pintype "passive"))
    )
    (net (code "51") (name "/D7") (class "Default")
      (node (ref "IC1") (pin "13") (pinfunction "D7_13") (pintype "bidirectional"))
      (node (ref "IC10") (pin "3") (pinfunction "Y4_3") (pintype "tri_state"))
      (node (ref "IC2") (pin "19") (pinfunction "O7_19") (pintype "tri_state"))
      (node (ref "IC22") (pin "17") (pinfunction "I/O4_17") (pintype "bidirectional"))
      (node (ref "IC24") (pin "17") (pinfunction "I/O4_17") (pintype "bidirectional"))
      (node (ref "R24") (pin "1") (pinfunction "1_1") (pintype "passive"))
      (node (ref "R8") (pin "2") (pinfunction "2_2") (pintype "passive"))
      (node (ref "U$1") (pin "3B") (pinfunction "EDGE_3B") (pintype "bidirectional"))
    )
    (net (code "52") (name "/D7'") (class "Default")
      (node (ref "IC13") (pin "14") (pinfunction "DO_14") (pintype "bidirectional"))
      (node (ref "IC13") (pin "2") (pinfunction "DI_2") (pintype "bidirectional"))
      (node (ref "IC3") (pin "32") (pinfunction "D7_32") (pintype "bidirectional"))
      (node (ref "R8") (pin "1") (pinfunction "1_1") (pintype "passive"))
    )
    (net (code "53") (name "/MREQ'") (class "Default")
      (node (ref "D10") (pin "C") (pinfunction "K_C") (pintype "bidirectional"))
      (node (ref "IC3") (pin "15") (pinfunction "~{MREQ}_15") (pintype "input"))
      (node (ref "R34") (pin "2") (pinfunction "2_2") (pintype "passive"))
    )
    (net (code "54") (name "/N$33") (class "Default")
      (node (ref "C26") (pin "1") (pinfunction "1_1") (pintype "passive"))
      (node (ref "C27") (pin "1") (pinfunction "1_1") (pintype "passive"))
      (node (ref "IC13") (pin "1") (pinfunction "VBB_1") (pintype "input"))
      (node (ref "IC14") (pin "1") (pinfunction "VBB_1") (pintype "input"))
      (node (ref "IC15") (pin "1") (pinfunction "VBB_1") (pintype "input"))
      (node (ref "IC16") (pin "1") (pinfunction "VBB_1") (pintype "input"))
      (node (ref "IC17") (pin "1") (pinfunction "VBB_1") (pintype "input"))
      (node (ref "IC18") (pin "1") (pinfunction "VBB_1") (pintype "input"))
      (node (ref "IC19") (pin "1") (pinfunction "VBB_1") (pintype "input"))
      (node (ref "IC20") (pin "1") (pinfunction "VBB_1") (pintype "input"))
      (node (ref "J3") (pin "2") (pinfunction "2_2") (pintype "passive"))
    )
    (net (code "55") (name "/RESET") (class "Default")
      (node (ref "D10") (pin "A") (pinfunction "A_A") (pintype "bidirectional"))
      (node (ref "IC28") (pin "12") (pinfunction "O_12") (pintype "output"))
    )
    (net (code "56") (name "/SNDIN") (class "Default")
      (node (ref "C54") (pin "1") (pinfunction "1_1") (pintype "passive"))
      (node (ref "C57") (pin "1") (pinfunction "1_1") (pintype "passive"))
      (node (ref "D13") (pin "A") (pinfunction "A_A") (pintype "bidirectional"))
      (node (ref "D14") (pin "C") (pinfunction "C_C") (pintype "passive"))
      (node (ref "Q7") (pin "2") (pinfunction "B_2") (pintype "passive"))
      (node (ref "R40") (pin "1") (pinfunction "1_1") (pintype "passive"))
      (node (ref "R41") (pin "2") (pinfunction "2_2") (pintype "passive"))
      (node (ref "R42") (pin "2") (pinfunction "2_2") (pintype "passive"))
      (node (ref "TP3") (pin "TP") (pinfunction "TP_TP") (pintype "input"))
    )
    (net (code "57") (name "/{slash}INT") (class "Default")
      (node (ref "IC1") (pin "16") (pinfunction "~{INT}_16") (pintype "input"))
      (node (ref "R25") (pin "2") (pinfunction "2_2") (pintype "passive"))
      (node (ref "TP10") (pin "TP") (pinfunction "TP_TP") (pintype "input"))
      (node (ref "U$1") (pin "13B") (pinfunction "EDGE_13B") (pintype "bidirectional"))
    )
    (net (code "58") (name "/~{A}{slash}B") (class "Default")
      (node (ref "IC27") (pin "3") (pinfunction "O_3") (pintype "output"))
      (node (ref "IC6") (pin "1") (pinfunction "~{A}/B_1") (pintype "input"))
      (node (ref "IC7") (pin "1") (pinfunction "~{A}/B_1") (pintype "input"))
      (node (ref "R45") (pin "1") (pinfunction "1_1") (pintype "passive"))
    )
    (net (code "59") (name "/~{CAS0}") (class "Default")
      (node (ref "IC23") (pin "1") (pinfunction "~{OE}_1") (pintype "input"))
      (node (ref "IC23") (pin "16") (pinfunction "~{CAS}_16") (pintype "input"))
      (node (ref "IC24") (pin "1") (pinfunction "~{OE}_1") (pintype "input"))
      (node (ref "IC24") (pin "16") (pinfunction "~{CAS}_16") (pintype "input"))
      (node (ref "IC25") (pin "8") (pinfunction "O_8") (pintype "output"))
    )
    (net (code "60") (name "/~{CAS1}") (class "Default")
      (node (ref "IC21") (pin "1") (pinfunction "~{OE}_1") (pintype "input"))
      (node (ref "IC21") (pin "16") (pinfunction "~{CAS}_16") (pintype "input"))
      (node (ref "IC22") (pin "1") (pinfunction "~{OE}_1") (pintype "input"))
      (node (ref "IC22") (pin "16") (pinfunction "~{CAS}_16") (pintype "input"))
      (node (ref "IC25") (pin "6") (pinfunction "O_6") (pintype "output"))
    )
    (net (code "61") (name "/~{IORQGE}") (class "Default")
      (node (ref "IC3") (pin "2") (pinfunction "~{CS}_2") (pintype "input"))
      (node (ref "Q1") (pin "1") (pinfunction "E_1") (pintype "passive"))
      (node (ref "R27") (pin "2") (pinfunction "2_2") (pintype "passive"))
      (node (ref "U$1") (pin "13A") (pinfunction "EDGE_13A") (pintype "bidirectional"))
    )
    (net (code "62") (name "/~{IORQ}") (class "Default")
      (node (ref "IC1") (pin "20") (pinfunction "~{IORQ}_20") (pintype "output"))
      (node (ref "R27") (pin "1") (pinfunction "1_1") (pintype "passive"))
      (node (ref "U$1") (pin "17B") (pinfunction "EDGE_17B") (pintype "bidirectional"))
    )
    (net (code "63") (name "/~{KBD}") (class "Default")
      (node (ref "IC10") (pin "1") (pinfunction "G_1") (pintype "input"))
      (node (ref "IC10") (pin "19") (pinfunction "G_19") (pintype "input"))
      (node (ref "IC3") (pin "10") (pinfunction "~{KBD}_10") (pintype "output"))
    )
    (net (code "64") (name "/~{MREQ}") (class "Default")
      (node (ref "IC1") (pin "19") (pinfunction "~{MREQ}_19") (pintype "output"))
      (node (ref "IC2") (pin "22") (pinfunction "~{OE}_22") (pintype "input"))
      (node (ref "IC27") (pin "4") (pinfunction "I0_4") (pintype "input"))
      (node (ref "R34") (pin "1") (pinfunction "1_1") (pintype "passive"))
      (node (ref "U$1") (pin "16B") (pinfunction "EDGE_16B") (pintype "bidirectional"))
    )
    (net (code "65") (name "/~{RAS}") (class "Default")
      (node (ref "IC21") (pin "5") (pinfunction "~{RAS}_5") (pintype "input"))
      (node (ref "IC22") (pin "5") (pinfunction "~{RAS}_5") (pintype "input"))
      (node (ref "IC23") (pin "5") (pinfunction "~{RAS}_5") (pintype "input"))
      (node (ref "IC24") (pin "5") (pinfunction "~{RAS}_5") (pintype "input"))
      (node (ref "IC27") (pin "6") (pinfunction "O_6") (pintype "output"))
      (node (ref "IC27") (pin "9") (pinfunction "I0_9") (pintype "input"))
      (node (ref "R28") (pin "1") (pinfunction "1_1") (pintype "passive"))
    )
    (net (code "66") (name "/~{RD}") (class "Default")
      (node (ref "IC1") (pin "21") (pinfunction "~{RD}_21") (pintype "output"))
      (node (ref "IC25") (pin "2") (pinfunction "I1_2") (pintype "input"))
      (node (ref "IC3") (pin "17") (pinfunction "~{RD}_17") (pintype "input"))
      (node (ref "J1") (pin "3") (pinfunction "3_3") (pintype "passive"))
      (node (ref "U$1") (pin "18B") (pinfunction "EDGE_18B") (pintype "bidirectional"))
    )
    (net (code "67") (name "/~{RESET}") (class "Default")
      (node (ref "C17") (pin "1") (pinfunction "1_1") (pintype "passive"))
      (node (ref "IC1") (pin "26") (pinfunction "~{RESET}_26") (pintype "input"))
      (node (ref "IC28") (pin "13") (pinfunction "I_13") (pintype "input"))
      (node (ref "R29") (pin "1") (pinfunction "1_1") (pintype "passive"))
      (node (ref "U$1") (pin "20A") (pinfunction "EDGE_20A") (pintype "bidirectional"))
    )
    (net (code "68") (name "/~{RFSH}") (class "Default")
      (node (ref "IC1") (pin "28") (pinfunction "~{RFSH}_28") (pintype "output"))
      (node (ref "IC26") (pin "13") (pinfunction "I1_13") (pintype "input"))
      (node (ref "IC26") (pin "2") (pinfunction "I1_2") (pintype "input"))
      (node (ref "IC5") (pin "11") (pinfunction "CLK_11") (pintype "input"))
      (node (ref "U$1") (pin "25B") (pinfunction "EDGE_25B") (pintype "bidirectional"))
    )
    (net (code "69") (name "/~{ROMCS}") (class "Default")
      (node (ref "IC2") (pin "20") (pinfunction "~{CE}_20") (pintype "input"))
      (node (ref "R26") (pin "2") (pinfunction "2_2") (pintype "passive"))
      (node (ref "TP9") (pin "TP") (pinfunction "TP_TP") (pintype "input"))
      (node (ref "U$1") (pin "25A") (pinfunction "EDGE_25A") (pintype "bidirectional"))
    )
    (net (code "70") (name "/~{ULAINT}") (class "Default")
      (node (ref "IC3") (pin "34") (pinfunction "~{INT}_34") (pintype "output"))
      (node (ref "R25") (pin "1") (pinfunction "1_1") (pintype "passive"))
    )
    (net (code "71") (name "/~{VCAS}") (class "Default")
      (node (ref "IC13") (pin "15") (pinfunction "~{CAS}_15") (pintype "input"))
      (node (ref "IC14") (pin "15") (pinfunction "~{CAS}_15") (pintype "input"))
      (node (ref "IC15") (pin "15") (pinfunction "~{CAS}_15") (pintype "input"))
      (node (ref "IC16") (pin "15") (pinfunction "~{CAS}_15") (pintype "input"))
      (node (ref "IC17") (pin "15") (pinfunction "~{CAS}_15") (pintype "input"))
      (node (ref "IC18") (pin "15") (pinfunction "~{CAS}_15") (pintype "input"))
      (node (ref "IC19") (pin "15") (pinfunction "~{CAS}_15") (pintype "input"))
      (node (ref "IC20") (pin "15") (pinfunction "~{CAS}_15") (pintype "input"))
      (node (ref "IC3") (pin "12") (pinfunction "~{VCAS}_12") (pintype "output"))
      (node (ref "TP5") (pin "TP") (pinfunction "TP_TP") (pintype "input"))
    )
    (net (code "72") (name "/~{VRAS}") (class "Default")
      (node (ref "IC13") (pin "4") (pinfunction "~{RAS}_4") (pintype "input"))
      (node (ref "IC14") (pin "4") (pinfunction "~{RAS}_4") (pintype "input"))
      (node (ref "IC15") (pin "4") (pinfunction "~{RAS}_4") (pintype "input"))
      (node (ref "IC16") (pin "4") (pinfunction "~{RAS}_4") (pintype "input"))
      (node (ref "IC17") (pin "4") (pinfunction "~{RAS}_4") (pintype "input"))
      (node (ref "IC18") (pin "4") (pinfunction "~{RAS}_4") (pintype "input"))
      (node (ref "IC19") (pin "4") (pinfunction "~{RAS}_4") (pintype "input"))
      (node (ref "IC20") (pin "4") (pinfunction "~{RAS}_4") (pintype "input"))
      (node (ref "IC3") (pin "13") (pinfunction "~{VRAS}_13") (pintype "output"))
      (node (ref "R16") (pin "2") (pinfunction "2_2") (pintype "passive"))
      (node (ref "TP4") (pin "TP") (pinfunction "TP_TP") (pintype "input"))
    )
    (net (code "73") (name "/~{VWR}") (class "Default")
      (node (ref "IC13") (pin "3") (pinfunction "~{WE}_3") (pintype "input"))
      (node (ref "IC14") (pin "3") (pinfunction "~{WE}_3") (pintype "input"))
      (node (ref "IC15") (pin "3") (pinfunction "~{WE}_3") (pintype "input"))
      (node (ref "IC16") (pin "3") (pinfunction "~{WE}_3") (pintype "input"))
      (node (ref "IC17") (pin "3") (pinfunction "~{WE}_3") (pintype "input"))
      (node (ref "IC18") (pin "3") (pinfunction "~{WE}_3") (pintype "input"))
      (node (ref "IC19") (pin "3") (pinfunction "~{WE}_3") (pintype "input"))
      (node (ref "IC20") (pin "3") (pinfunction "~{WE}_3") (pintype "input"))
      (node (ref "IC3") (pin "14") (pinfunction "~{VWR}_14") (pintype "output"))
      (node (ref "TP6") (pin "TP") (pinfunction "TP_TP") (pintype "input"))
    )
    (net (code "74") (name "/~{WR}") (class "Default")
      (node (ref "IC1") (pin "22") (pinfunction "~{WR}_22") (pintype "output"))
      (node (ref "IC21") (pin "4") (pinfunction "~{WE}_4") (pintype "input"))
      (node (ref "IC22") (pin "4") (pinfunction "~{WE}_4") (pintype "input"))
      (node (ref "IC23") (pin "4") (pinfunction "~{WE}_4") (pintype "input"))
      (node (ref "IC24") (pin "4") (pinfunction "~{WE}_4") (pintype "input"))
      (node (ref "IC25") (pin "1") (pinfunction "I0_1") (pintype "input"))
      (node (ref "IC3") (pin "16") (pinfunction "~{WR}_16") (pintype "input"))
      (node (ref "U$1") (pin "19B") (pinfunction "EDGE_19B") (pintype "bidirectional"))
    )
    (net (code "75") (name "AUDIO") (class "Default")
      (node (ref "C36") (pin "2") (pinfunction "2_2") (pintype "passive"))
      (node (ref "C54") (pin "2") (pinfunction "2_2") (pintype "passive"))
      (node (ref "C55") (pin "1") (pinfunction "1_1") (pintype "passive"))
      (node (ref "D25_") (pin "A") (pinfunction "A_A") (pintype "bidirectional"))
      (node (ref "J4") (pin "1") (pinfunction "1_1") (pintype "passive"))
      (node (ref "R53") (pin "1") (pinfunction "1_1") (pintype "passive"))
      (node (ref "R54") (pin "2") (pinfunction "2_2") (pintype "passive"))
    )
    (net (code "76") (name "GND") (class "Default")
      (node (ref "7805") (pin "GND") (pinfunction "GND_GND") (pintype "input"))
      (node (ref "C1") (pin "-") (pinfunction "-_-") (pintype "passive"))
      (node (ref "C10") (pin "2") (pinfunction "2_2") (pintype "passive"))
      (node (ref "C11") (pin "2") (pinfunction "2_2") (pintype "passive"))
      (node (ref "C12") (pin "1") (pinfunction "1_1") (pintype "passive"))
      (node (ref "C13") (pin "1") (pinfunction "1_1") (pintype "passive"))
      (node (ref "C14") (pin "1") (pinfunction "1_1") (pintype "passive"))
      (node (ref "C15") (pin "2") (pinfunction "2_2") (pintype "passive"))
      (node (ref "C16") (pin "2") (pinfunction "2_2") (pintype "passive"))
      (node (ref "C17") (pin "2") (pinfunction "2_2") (pintype "passive"))
      (node (ref "C18") (pin "2") (pinfunction "2_2") (pintype "passive"))
      (node (ref "C19") (pin "2") (pinfunction "2_2") (pintype "passive"))
      (node (ref "C2") (pin "-") (pinfunction "-_-") (pintype "passive"))
      (node (ref "C20") (pin "2") (pinfunction "2_2") (pintype "passive"))
      (node (ref "C21") (pin "2") (pinfunction "2_2") (pintype "passive"))
      (node (ref "C22") (pin "1") (pinfunction "1_1") (pintype "passive"))
      (node (ref "C23") (pin "2") (pinfunction "2_2") (pintype "passive"))
      (node (ref "C24") (pin "1") (pinfunction "1_1") (pintype "passive"))
      (node (ref "C25") (pin "2") (pinfunction "2_2") (pintype "passive"))
      (node (ref "C26") (pin "2") (pinfunction "2_2") (pintype "passive"))
      (node (ref "C27") (pin "2") (pinfunction "2_2") (pintype "passive"))
      (node (ref "C28") (pin "2") (pinfunction "2_2") (pintype "passive"))
      (node (ref "C29") (pin "1") (pinfunction "1_1") (pintype "passive"))
      (node (ref "C3") (pin "1") (pinfunction "1_1") (pintype "passive"))
      (node (ref "C30") (pin "2") (pinfunction "2_2") (pintype "passive"))
      (node (ref "C31") (pin "1") (pinfunction "1_1") (pintype "passive"))
      (node (ref "C32") (pin "1") (pinfunction "1_1") (pintype "passive"))
      (node (ref "C33") (pin "1") (pinfunction "1_1") (pintype "passive"))
      (node (ref "C40") (pin "1") (pinfunction "1_1") (pintype "passive"))
      (node (ref "C43") (pin "1") (pinfunction "1_1") (pintype "passive"))
      (node (ref "C44") (pin "2") (pinfunction "2_2") (pintype "passive"))
      (node (ref "C45") (pin "2") (pinfunction "2_2") (pintype "passive"))
      (node (ref "C46") (pin "2") (pinfunction "2_2") (pintype "passive"))
      (node (ref "C49") (pin "+") (pinfunction "+_+") (pintype "passive"))
      (node (ref "C50") (pin "2") (pinfunction "2_2") (pintype "passive"))
      (node (ref "C52") (pin "-") (pinfunction "-_-") (pintype "passive"))
      (node (ref "C53") (pin "-") (pinfunction "-_-") (pintype "passive"))
      (node (ref "C56") (pin "1") (pinfunction "1_1") (pintype "passive"))
      (node (ref "C57") (pin "2") (pinfunction "2_2") (pintype "passive"))
      (node (ref "C6") (pin "1") (pinfunction "1_1") (pintype "passive"))
      (node (ref "C8") (pin "1") (pinfunction "1_1") (pintype "passive"))
      (node (ref "D14") (pin "A") (pinfunction "A_A") (pintype "passive"))
      (node (ref "D16") (pin "A") (pinfunction "A_A") (pintype "bidirectional"))
      (node (ref "D18") (pin "A") (pinfunction "A_A") (pintype "bidirectional"))
      (node (ref "D20") (pin "C") (pinfunction "K_C") (pintype "bidirectional"))
      (node (ref "D21") (pin "C") (pinfunction "K_C") (pintype "bidirectional"))
      (node (ref "D24") (pin "A") (pinfunction "A_A") (pintype "bidirectional"))
      (node (ref "EAR") (pin "RING") (pinfunction "SHIELD_RING") (pintype "passive"))
      (node (ref "IC1") (pin "29") (pinfunction "GND_29") (pintype "power_in"))
      (node (ref "IC10") (pin "10") (pinfunction "GND_10") (pintype "power_in"))
      (node (ref "IC11") (pin "10") (pinfunction "GND_10") (pintype "power_in"))
      (node (ref "IC12") (pin "5") (pinfunction "GND_5") (pintype "power_in"))
      (node (ref "IC13") (pin "16") (pinfunction "VSS_16") (pintype "power_in"))
      (node (ref "IC14") (pin "16") (pinfunction "VSS_16") (pintype "power_in"))
      (node (ref "IC15") (pin "16") (pinfunction "VSS_16") (pintype "power_in"))
      (node (ref "IC16") (pin "16") (pinfunction "VSS_16") (pintype "power_in"))
      (node (ref "IC17") (pin "16") (pinfunction "VSS_16") (pintype "power_in"))
      (node (ref "IC18") (pin "16") (pinfunction "VSS_16") (pintype "power_in"))
      (node (ref "IC19") (pin "16") (pinfunction "VSS_16") (pintype "power_in"))
      (node (ref "IC2") (pin "14") (pinfunction "GND_14") (pintype "power_in"))
      (node (ref "IC20") (pin "16") (pinfunction "VSS_16") (pintype "power_in"))
      (node (ref "IC21") (pin "18") (pinfunction "GND_18") (pintype "power_in"))
      (node (ref "IC22") (pin "18") (pinfunction "GND_18") (pintype "power_in"))
      (node (ref "IC23") (pin "18") (pinfunction "GND_18") (pintype "power_in"))
      (node (ref "IC24") (pin "18") (pinfunction "GND_18") (pintype "power_in"))
      (node (ref "IC25") (pin "7") (pinfunction "GND_7") (pintype "power_in"))
      (node (ref "IC26") (pin "7") (pinfunction "GND_7") (pintype "power_in"))
      (node (ref "IC27") (pin "5") (pinfunction "I1_5") (pintype "input"))
      (node (ref "IC27") (pin "7") (pinfunction "GND_7") (pintype "power_in"))
      (node (ref "IC28") (pin "7") (pinfunction "GND_7") (pintype "power_in"))
      (node (ref "IC3") (pin "20") (pinfunction "GND_20") (pintype "power_in"))
      (node (ref "IC4") (pin "7") (pinfunction "GND_7") (pintype "power_in"))
      (node (ref "IC5") (pin "7") (pinfunction "GND_7") (pintype "power_in"))
      (node (ref "IC6") (pin "15") (pinfunction "G_15") (pintype "input"))
      (node (ref "IC6") (pin "8") (pinfunction "GND_8") (pintype "power_in"))
      (node (ref "IC7") (pin "15") (pinfunction "G_15") (pintype "input"))
      (node (ref "IC7") (pin "8") (pinfunction "GND_8") (pintype "power_in"))
      (node (ref "IC8") (pin "15") (pinfunction "G_15") (pintype "input"))
      (node (ref "IC8") (pin "8") (pinfunction "GND_8") (pintype "power_in"))
      (node (ref "IC9") (pin "15") (pinfunction "G_15") (pintype "input"))
      (node (ref "IC9") (pin "8") (pinfunction "GND_8") (pintype "power_in"))
      (node (ref "MIC") (pin "RING") (pinfunction "SHIELD_RING") (pintype "passive"))
      (node (ref "Q2") (pin "1") (pinfunction "E_1") (pintype "passive"))
      (node (ref "Q4") (pin "1") (pinfunction "E_1") (pintype "passive"))
      (node (ref "Q6") (pin "C") (pinfunction "C_C") (pintype "passive"))
      (node (ref "Q7") (pin "1") (pinfunction "E_1") (pintype "passive"))
      (node (ref "R33") (pin "2") (pinfunction "2_2") (pintype "passive"))
      (node (ref "R41") (pin "1") (pinfunction "1_1") (pintype "passive"))
      (node (ref "R47") (pin "1") (pinfunction "1_1") (pintype "passive"))
      (node (ref "R50") (pin "1") (pinfunction "1_1") (pintype "passive"))
      (node (ref "R53") (pin "2") (pinfunction "2_2") (pintype "passive"))
      (node (ref "R55") (pin "2") (pinfunction "2_2") (pintype "passive"))
      (node (ref "R65") (pin "2") (pinfunction "2_2") (pintype "passive"))
      (node (ref "R69") (pin "1") (pinfunction "1_1") (pintype "passive"))
      (node (ref "R70") (pin "1") (pinfunction "1_1") (pintype "passive"))
      (node (ref "R73_") (pin "2") (pinfunction "2_2") (pintype "passive"))
      (node (ref "R76") (pin "2") (pinfunction "2_2") (pintype "passive"))
      (node (ref "U$1") (pin "14A") (pinfunction "EDGE_14A") (pintype "bidirectional"))
      (node (ref "U$1") (pin "6A") (pinfunction "EDGE_6A") (pintype "bidirectional"))
      (node (ref "U$1") (pin "7A") (pinfunction "EDGE_7A") (pintype "bidirectional"))
      (node (ref "X1") (pin "2") (pinfunction "2_2") (pintype "passive"))
      (node (ref "X1") (pin "2@1") (pinfunction "2_2@1") (pintype "passive"))
      (node (ref "X1") (pin "2@2") (pinfunction "2_2@2") (pintype "passive"))
      (node (ref "X2") (pin "RING") (pinfunction "SHIELD_RING") (pintype "passive"))
    )
    (net (code "77") (name "Net-(C5-Pad+)") (class "Default")
      (node (ref "C5") (pin "+") (pinfunction "+_+") (pintype "passive"))
      (node (ref "R42") (pin "1") (pinfunction "1_1") (pintype "passive"))
    )
    (net (code "78") (name "Net-(C5-Pad-)") (class "Default")
      (node (ref "C5") (pin "-") (pinfunction "-_-") (pintype "passive"))
      (node (ref "EAR") (pin "TIP") (pinfunction "TIP_TIP") (pintype "passive"))
      (node (ref "J5") (pin "1") (pinfunction "1_1") (pintype "passive"))
      (node (ref "R70") (pin "2") (pinfunction "2_2") (pintype "passive"))
    )
    (net (code "79") (name "Net-(C7-Pad1)") (class "Default")
      (node (ref "C7") (pin "1") (pinfunction "1_1") (pintype "passive"))
      (node (ref "XTAL") (pin "2") (pinfunction "2_2") (pintype "passive"))
    )
    (net (code "80") (name "Net-(C8-Pad2)") (class "Default")
      (node (ref "C8") (pin "2") (pinfunction "2_2") (pintype "passive"))
      (node (ref "Q3") (pin "B") (pinfunction "B_B") (pintype "passive"))
      (node (ref "R44") (pin "2") (pinfunction "2_2") (pintype "passive"))
      (node (ref "XTAL") (pin "1") (pinfunction "1_1") (pintype "passive"))
    )
    (net (code "81") (name "Net-(C37-Pad1)") (class "Default")
      (node (ref "C37") (pin "1") (pinfunction "1_1") (pintype "passive"))
      (node (ref "C38") (pin "2") (pinfunction "2_2") (pintype "passive"))
      (node (ref "R55") (pin "1") (pinfunction "1_1") (pintype "passive"))
    )
    (net (code "82") (name "Net-(C38-Pad1)") (class "Default")
      (node (ref "C38") (pin "1") (pinfunction "1_1") (pintype "passive"))
      (node (ref "C39") (pin "2") (pinfunction "2_2") (pintype "passive"))
      (node (ref "R56") (pin "1") (pinfunction "1_1") (pintype "passive"))
    )
    (net (code "83") (name "Net-(C39-Pad1)") (class "Default")
      (node (ref "C39") (pin "1") (pinfunction "1_1") (pintype "passive"))
      (node (ref "L2") (pin "2") (pinfunction "2_2") (pintype "passive"))
    )
    (net (code "84") (name "Net-(C49-Pad-)") (class "Default")
      (node (ref "C49") (pin "-") (pinfunction "-_-") (pintype "passive"))
      (node (ref "D19") (pin "A") (pinfunction "A_A") (pintype "bidirectional"))
      (node (ref "R67") (pin "2") (pinfunction "2_2") (pintype "passive"))
    )
    (net (code "85") (name "Net-(C56-Pad2)") (class "Default")
      (node (ref "C56") (pin "2") (pinfunction "2_2") (pintype "passive"))
      (node (ref "L2") (pin "1") (pinfunction "1_1") (pintype "passive"))
      (node (ref "R71") (pin "1") (pinfunction "1_1") (pintype "passive"))
      (node (ref "R72") (pin "2") (pinfunction "2_2") (pintype "passive"))
    )
    (net (code "86") (name "Net-(C58-Pad+)") (class "Default")
      (node (ref "C58") (pin "+") (pinfunction "+_+") (pintype "passive"))
      (node (ref "R77") (pin "2") (pinfunction "2_2") (pintype "passive"))
    )
    (net (code "87") (name "Net-(C58-Pad-)") (class "Default")
      (node (ref "C58") (pin "-") (pinfunction "-_-") (pintype "passive"))
      (node (ref "X1") (pin "1") (pinfunction "1_1") (pintype "passive"))
    )
    (net (code "88") (name "Net-(D2-PadA)") (class "Default")
      (node (ref "D2") (pin "A") (pinfunction "A_A") (pintype "bidirectional"))
      (node (ref "KB2") (pin "3") (pinfunction "3_3") (pintype "passive"))
    )
    (net (code "89") (name "Net-(D3-PadA)") (class "Default")
      (node (ref "D3") (pin "A") (pinfunction "A_A") (pintype "bidirectional"))
      (node (ref "KB2") (pin "6") (pinfunction "6_6") (pintype "passive"))
    )
    (net (code "90") (name "Net-(D4-PadA)") (class "Default")
      (node (ref "D4") (pin "A") (pinfunction "A_A") (pintype "bidirectional"))
      (node (ref "KB2") (pin "7") (pinfunction "7_7") (pintype "passive"))
    )
    (net (code "91") (name "Net-(D7-PadA)") (class "Default")
      (node (ref "D7") (pin "A") (pinfunction "A_A") (pintype "bidirectional"))
      (node (ref "KB2") (pin "4") (pinfunction "4_4") (pintype "passive"))
    )
    (net (code "92") (name "Net-(D8-PadA)") (class "Default")
      (node (ref "D8") (pin "A") (pinfunction "A_A") (pintype "bidirectional"))
      (node (ref "KB2") (pin "2") (pinfunction "2_2") (pintype "passive"))
    )
    (net (code "93") (name "Net-(D9-PadA)") (class "Default")
      (node (ref "D9") (pin "A") (pinfunction "A_A") (pintype "bidirectional"))
      (node (ref "KB2") (pin "1") (pinfunction "1_1") (pintype "passive"))
    )
    (net (code "94") (name "Net-(D11-K)") (class "Default")
      (node (ref "D11") (pin "C") (pinfunction "K_C") (pintype "bidirectional"))
      (node (ref "D12") (pin "C") (pinfunction "K_C") (pintype "bidirectional"))
      (node (ref "IC27") (pin "11") (pinfunction "O_11") (pintype "output"))
      (node (ref "R26") (pin "1") (pinfunction "1_1") (pintype "passive"))
      (node (ref "R33") (pin "1") (pinfunction "1_1") (pintype "passive"))
    )
    (net (code "95") (name "Net-(D16-K)") (class "Default")
      (node (ref "C36") (pin "1") (pinfunction "1_1") (pintype "passive"))
      (node (ref "D15") (pin "A") (pinfunction "A_A") (pintype "bidirectional"))
      (node (ref "D16") (pin "C") (pinfunction "K_C") (pintype "bidirectional"))
      (node (ref "IC3") (pin "24") (pinfunction "BEEP_24") (pintype "output"))
      (node (ref "TP7") (pin "TP") (pinfunction "TP_TP") (pintype "input"))
    )
    (net (code "96") (name "Net-(D19-K)") (class "Default")
      (node (ref "C48") (pin "2") (pinfunction "2_2") (pintype "passive"))
      (node (ref "D19") (pin "C") (pinfunction "K_C") (pintype "bidirectional"))
      (node (ref "D20") (pin "A") (pinfunction "A_A") (pintype "bidirectional"))
    )
    (net (code "97") (name "Net-(D22-K)") (class "Default")
      (node (ref "C51") (pin "2") (pinfunction "2_2") (pintype "passive"))
      (node (ref "D22") (pin "C") (pinfunction "K_C") (pintype "bidirectional"))
      (node (ref "D23") (pin "A") (pinfunction "A_A") (pintype "bidirectional"))
    )
    (net (code "98") (name "Net-(D23-K)") (class "Default")
      (node (ref "C52") (pin "+") (pinfunction "+_+") (pintype "passive"))
      (node (ref "D23") (pin "C") (pinfunction "K_C") (pintype "bidirectional"))
      (node (ref "R68") (pin "2") (pinfunction "2_2") (pintype "passive"))
    )
    (net (code "99") (name "Net-(D27-K)") (class "Default")
      (node (ref "D25") (pin "C") (pinfunction "C_C") (pintype "passive"))
      (node (ref "D26") (pin "C") (pinfunction "C_C") (pintype "passive"))
      (node (ref "D27") (pin "C") (pinfunction "K_C") (pintype "bidirectional"))
      (node (ref "IC3") (pin "18") (pinfunction "BRIGHT_18") (pintype "output"))
    )
    (net (code "100") (name "Net-(EAR-PadNC)") (class "Default")
      (node (ref "EAR") (pin "NC") (pinfunction "NC_NC") (pintype "passive"))
      (node (ref "J5") (pin "2") (pinfunction "2_2") (pintype "passive"))
    )
    (net (code "101") (name "Net-(IC1-CLK)") (class "Default")
      (node (ref "IC1") (pin "6") (pinfunction "CLK_6") (pintype "input"))
      (node (ref "Q2") (pin "3") (pinfunction "C_3") (pintype "passive"))
      (node (ref "R48") (pin "1") (pinfunction "1_1") (pintype "passive"))
      (node (ref "TP1") (pin "TP") (pinfunction "TP_TP") (pintype "input"))
    )
    (net (code "102") (name "Net-(IC1-~{BUSAK})") (class "Default")
      (node (ref "IC1") (pin "23") (pinfunction "~{BUSAK}_23") (pintype "output"))
      (node (ref "U$1") (pin "26A") (pinfunction "EDGE_26A") (pintype "bidirectional"))
    )
    (net (code "103") (name "Net-(IC1-~{BUSRQ})") (class "Default")
      (node (ref "IC1") (pin "25") (pinfunction "~{BUSRQ}_25") (pintype "input"))
      (node (ref "R30") (pin "2") (pinfunction "2_2") (pintype "passive"))
      (node (ref "U$1") (pin "19A") (pinfunction "EDGE_19A") (pintype "bidirectional"))
    )
    (net (code "104") (name "Net-(IC1-~{HALT})") (class "Default")
      (node (ref "IC1") (pin "18") (pinfunction "~{HALT}_18") (pintype "output"))
      (node (ref "U$1") (pin "15B") (pinfunction "EDGE_15B") (pintype "bidirectional"))
    )
    (net (code "105") (name "Net-(IC1-~{M1})") (class "Default")
      (node (ref "IC1") (pin "27") (pinfunction "~{M1}_27") (pintype "output"))
      (node (ref "U$1") (pin "24B") (pinfunction "EDGE_24B") (pintype "bidirectional"))
    )
    (net (code "106") (name "Net-(IC1-~{NMI})") (class "Default")
      (node (ref "IC1") (pin "17") (pinfunction "~{NMI}_17") (pintype "input"))
      (node (ref "R31") (pin "2") (pinfunction "2_2") (pintype "passive"))
      (node (ref "U$1") (pin "14B") (pinfunction "EDGE_14B") (pintype "bidirectional"))
    )
    (net (code "107") (name "Net-(IC1-~{WAIT})") (class "Default")
      (node (ref "IC1") (pin "24") (pinfunction "~{WAIT}_24") (pintype "input"))
      (node (ref "R32") (pin "2") (pinfunction "2_2") (pintype "passive"))
      (node (ref "U$1") (pin "21B") (pinfunction "EDGE_21B") (pintype "bidirectional"))
    )
    (net (code "108") (name "Net-(IC2-~{PGM})") (class "Default")
      (node (ref "IC2") (pin "27") (pinfunction "~{PGM}_27") (pintype "input"))
      (node (ref "J1") (pin "2") (pinfunction "2_2") (pintype "passive"))
    )
    (net (code "109") (name "Net-(IC3-MIC)") (class "Default")
      (node (ref "IC3") (pin "23") (pinfunction "MIC_23") (pintype "output"))
      (node (ref "R46") (pin "2") (pinfunction "2_2") (pintype "passive"))
    )
    (net (code "110") (name "Net-(IC4B-D)") (class "Default")
      (node (ref "IC4") (pin "12") (pinfunction "D_12") (pintype "input"))
      (node (ref "IC4") (pin "8") (pinfunction "~{Q}_8") (pintype "output"))
    )
    (net (code "111") (name "Net-(IC5A-CLK)") (class "Default")
      (node (ref "IC5") (pin "3") (pinfunction "CLK_3") (pintype "input"))
      (node (ref "IC5") (pin "9") (pinfunction "Q_9") (pintype "output"))
    )
    (net (code "112") (name "Net-(IC5A-D)") (class "Default")
      (node (ref "IC5") (pin "2") (pinfunction "D_2") (pintype "input"))
      (node (ref "IC5") (pin "6") (pinfunction "~{Q}_6") (pintype "output"))
    )
    (net (code "113") (name "Net-(IC8A-1Y)") (class "Default")
      (node (ref "IC8") (pin "4") (pinfunction "1Y_4") (pintype "output"))
      (node (ref "R15") (pin "2") (pinfunction "2_2") (pintype "passive"))
    )
    (net (code "114") (name "Net-(IC8A-2Y)") (class "Default")
      (node (ref "IC8") (pin "7") (pinfunction "2Y_7") (pintype "output"))
      (node (ref "R14") (pin "2") (pinfunction "2_2") (pintype "passive"))
    )
    (net (code "115") (name "Net-(IC8A-3Y)") (class "Default")
      (node (ref "IC8") (pin "9") (pinfunction "3Y_9") (pintype "output"))
      (node (ref "R12") (pin "2") (pinfunction "2_2") (pintype "passive"))
    )
    (net (code "116") (name "Net-(IC8A-4Y)") (class "Default")
      (node (ref "IC8") (pin "12") (pinfunction "4Y_12") (pintype "output"))
      (node (ref "R13") (pin "2") (pinfunction "2_2") (pintype "passive"))
    )
    (net (code "117") (name "Net-(IC8A-~{A}{slash}B)") (class "Default")
      (node (ref "IC8") (pin "1") (pinfunction "~{A}/B_1") (pintype "input"))
      (node (ref "IC9") (pin "1") (pinfunction "~{A}/B_1") (pintype "input"))
      (node (ref "R16") (pin "1") (pinfunction "1_1") (pintype "passive"))
    )
    (net (code "118") (name "Net-(IC9A-2Y)") (class "Default")
      (node (ref "IC9") (pin "7") (pinfunction "2Y_7") (pintype "output"))
      (node (ref "R11") (pin "2") (pinfunction "2_2") (pintype "passive"))
    )
    (net (code "119") (name "Net-(IC9A-3Y)") (class "Default")
      (node (ref "IC9") (pin "9") (pinfunction "3Y_9") (pintype "output"))
      (node (ref "R9") (pin "2") (pinfunction "2_2") (pintype "passive"))
    )
    (net (code "120") (name "Net-(IC9A-4Y)") (class "Default")
      (node (ref "IC9") (pin "12") (pinfunction "4Y_12") (pintype "output"))
      (node (ref "R10") (pin "2") (pinfunction "2_2") (pintype "passive"))
    )
    (net (code "121") (name "Net-(IC10A-A1)") (class "Default")
      (node (ref "IC10") (pin "2") (pinfunction "A1_2") (pintype "input"))
      (node (ref "KB1") (pin "5") (pinfunction "5_5") (pintype "passive"))
      (node (ref "P") (pin "6") (pinfunction "M_6") (pintype "passive"))
      (node (ref "R39") (pin "2") (pinfunction "2_2") (pintype "passive"))
    )
    (net (code "122") (name "Net-(IC10A-A2)") (class "Default")
      (node (ref "IC10") (pin "4") (pinfunction "A2_4") (pintype "input"))
      (node (ref "KB1") (pin "4") (pinfunction "4_4") (pintype "passive"))
      (node (ref "P") (pin "1") (pinfunction "M_1") (pintype "passive"))
      (node (ref "R38") (pin "2") (pinfunction "2_2") (pintype "passive"))
    )
    (net (code "123") (name "Net-(IC10A-A3)") (class "Default")
      (node (ref "IC10") (pin "6") (pinfunction "A3_6") (pintype "input"))
      (node (ref "KB1") (pin "3") (pinfunction "3_3") (pintype "passive"))
      (node (ref "P") (pin "2") (pinfunction "M_2") (pintype "passive"))
      (node (ref "R35") (pin "2") (pinfunction "2_2") (pintype "passive"))
    )
    (net (code "124") (name "Net-(IC10A-A4)") (class "Default")
      (node (ref "IC10") (pin "8") (pinfunction "A4_8") (pintype "input"))
      (node (ref "KB1") (pin "2") (pinfunction "2_2") (pintype "passive"))
      (node (ref "P") (pin "4") (pinfunction "M_4") (pintype "passive"))
      (node (ref "R36") (pin "2") (pinfunction "2_2") (pintype "passive"))
    )
    (net (code "125") (name "Net-(IC10B-A1)") (class "Default")
      (node (ref "IC10") (pin "11") (pinfunction "A1_11") (pintype "input"))
      (node (ref "KB1") (pin "1") (pinfunction "1_1") (pintype "passive"))
      (node (ref "P") (pin "3") (pinfunction "M_3") (pintype "passive"))
      (node (ref "R37") (pin "2") (pinfunction "2_2") (pintype "passive"))
    )
    (net (code "126") (name "Net-(IC10B-A3)") (class "Default")
      (node (ref "IC10") (pin "15") (pinfunction "A3_15") (pintype "input"))
      (node (ref "Q7") (pin "3") (pinfunction "C_3") (pintype "passive"))
      (node (ref "R74_") (pin "1") (pinfunction "1_1") (pintype "passive"))
    )
    (net (code "127") (name "Net-(IC11-B-Y)") (class "Default")
      (node (ref "C45") (pin "1") (pinfunction "1_1") (pintype "passive"))
      (node (ref "IC11") (pin "4") (pinfunction "B-Y_4") (pintype "output"))
      (node (ref "IC12") (pin "4") (pinfunction "B-Y_4") (pintype "input"))
    )
    (net (code "128") (name "Net-(IC11-B1)") (class "Default")
      (node (ref "IC11") (pin "17") (pinfunction "B3_17") (pintype "input"))
      (node (ref "IC11") (pin "19") (pinfunction "B1_19") (pintype "input"))
      (node (ref "IC3") (pin "22") (pinfunction "BLUE_22") (pintype "output"))
      (node (ref "R75") (pin "2") (pinfunction "2_2") (pintype "passive"))
    )
    (net (code "129") (name "Net-(IC11-B2)") (class "Default")
      (node (ref "D27") (pin "A") (pinfunction "A_A") (pintype "bidirectional"))
      (node (ref "IC11") (pin "18") (pinfunction "B2_18") (pintype "input"))
      (node (ref "R75") (pin "1") (pinfunction "1_1") (pintype "passive"))
    )
    (net (code "130") (name "Net-(IC11-BLANK)") (class "Default")
      (node (ref "IC11") (pin "8") (pinfunction "SYNC_8") (pintype "input"))
      (node (ref "IC11") (pin "9") (pinfunction "BLANK_9") (pintype "input"))
      (node (ref "IC3") (pin "33") (pinfunction "SYNC_33") (pintype "output"))
      (node (ref "TP8") (pin "TP") (pinfunction "TP_TP") (pintype "input"))
    )
    (net (code "131") (name "Net-(IC11-CREF)") (class "Default")
      (node (ref "C46") (pin "1") (pinfunction "1_1") (pintype "passive"))
      (node (ref "IC11") (pin "7") (pinfunction "CREF_7") (pintype "input"))
      (node (ref "IC12") (pin "12") (pinfunction "Y_12") (pintype "input"))
    )
    (net (code "132") (name "Net-(IC11-G1)") (class "Default")
      (node (ref "IC11") (pin "14") (pinfunction "G3_14") (pintype "input"))
      (node (ref "IC11") (pin "16") (pinfunction "G1_16") (pintype "input"))
      (node (ref "IC3") (pin "19") (pinfunction "GREEN_19") (pintype "output"))
      (node (ref "R73") (pin "2") (pinfunction "2_2") (pintype "passive"))
    )
    (net (code "133") (name "Net-(IC11-G2)") (class "Default")
      (node (ref "D25") (pin "A") (pinfunction "A_A") (pintype "passive"))
      (node (ref "IC11") (pin "15") (pinfunction "G2_15") (pintype "input"))
      (node (ref "R73") (pin "1") (pinfunction "1_1") (pintype "passive"))
    )
    (net (code "134") (name "Net-(IC11-GATE)") (class "Default")
      (node (ref "IC11") (pin "1") (pinfunction "GATE_1") (pintype "input"))
      (node (ref "IC28") (pin "6") (pinfunction "O_6") (pintype "output"))
    )
    (net (code "135") (name "Net-(IC11-H{slash}2)") (class "Default")
      (node (ref "IC11") (pin "2") (pinfunction "H/2_2") (pintype "input"))
      (node (ref "IC4") (pin "9") (pinfunction "Q_9") (pintype "output"))
    )
    (net (code "136") (name "Net-(IC11-R-Y)") (class "Default")
      (node (ref "C44") (pin "1") (pinfunction "1_1") (pintype "passive"))
      (node (ref "IC11") (pin "3") (pinfunction "R-Y_3") (pintype "output"))
      (node (ref "IC12") (pin "2") (pinfunction "R-Y_2") (pintype "input"))
    )
    (net (code "137") (name "Net-(IC11-R1)") (class "Default")
      (node (ref "IC11") (pin "11") (pinfunction "R3_11") (pintype "input"))
      (node (ref "IC11") (pin "13") (pinfunction "R1_13") (pintype "input"))
      (node (ref "IC3") (pin "21") (pinfunction "RED_21") (pintype "output"))
      (node (ref "R74") (pin "2") (pinfunction "2_2") (pintype "passive"))
    )
    (net (code "138") (name "Net-(IC11-R2)") (class "Default")
      (node (ref "D26") (pin "A") (pinfunction "A_A") (pintype "passive"))
      (node (ref "IC11") (pin "12") (pinfunction "R2_12") (pintype "input"))
      (node (ref "R74") (pin "1") (pinfunction "1_1") (pintype "passive"))
    )
    (net (code "139") (name "Net-(IC11-Y)") (class "Default")
      (node (ref "IC11") (pin "6") (pinfunction "Y_6") (pintype "output"))
      (node (ref "R63") (pin "2") (pinfunction "2_2") (pintype "passive"))
    )
    (net (code "140") (name "Net-(IC12-CHB_O)") (class "Default")
      (node (ref "IC12") (pin "10") (pinfunction "CHB_O_10") (pintype "input"))
      (node (ref "R59") (pin "2") (pinfunction "2_2") (pintype "passive"))
    )
    (net (code "141") (name "Net-(IC12-CR_LAG)") (class "Default")
      (node (ref "C40") (pin "2") (pinfunction "2_2") (pintype "passive"))
      (node (ref "IC12") (pin "18") (pinfunction "CR_LAG_18") (pintype "output"))
      (node (ref "R56") (pin "2") (pinfunction "2_2") (pintype "passive"))
    )
    (net (code "142") (name "Net-(IC12-CR_LEAD)") (class "Default")
      (node (ref "C37") (pin "2") (pinfunction "2_2") (pintype "passive"))
      (node (ref "IC12") (pin "1") (pinfunction "CR_LEAD_1") (pintype "input"))
    )
    (net (code "143") (name "Net-(IC12-CR_OSC)") (class "Default")
      (node (ref "IC12") (pin "17") (pinfunction "CR_OSC_17") (pintype "input"))
      (node (ref "R72") (pin "1") (pinfunction "1_1") (pintype "passive"))
      (node (ref "R73_") (pin "1") (pinfunction "1_1") (pintype "passive"))
    )
    (net (code "144") (name "Net-(IC12-CR_SUBC)") (class "Default")
      (node (ref "IC12") (pin "13") (pinfunction "CR_SUBC_13") (pintype "input"))
      (node (ref "Q8") (pin "2") (pinfunction "B_2") (pintype "passive"))
      (node (ref "R63") (pin "1") (pinfunction "1_1") (pintype "passive"))
    )
    (net (code "145") (name "Net-(IC12-SNDTK)") (class "Default")
      (node (ref "D25_") (pin "K") (pinfunction "K_K") (pintype "bidirectional"))
      (node (ref "IC12") (pin "15") (pinfunction "SNDTK_15") (pintype "input"))
      (node (ref "L1") (pin "4") (pinfunction "E_4") (pintype "passive"))
    )
    (net (code "146") (name "Net-(IC12-TNKA1)") (class "Default")
      (node (ref "IC12") (pin "8") (pinfunction "TNKA1_8") (pintype "output"))
      (node (ref "IC12") (pin "9") (pinfunction "TNKA2_9") (pintype "input"))
    )
    (net (code "147") (name "Net-(IC12-TNKB1)") (class "Default")
      (node (ref "C41") (pin "2") (pinfunction "2_2") (pintype "passive"))
      (node (ref "IC12") (pin "6") (pinfunction "TNKB1_6") (pintype "output"))
      (node (ref "L3") (pin "1") (pinfunction "1_1") (pintype "passive"))
      (node (ref "R57") (pin "2") (pinfunction "2_2") (pintype "passive"))
    )
    (net (code "148") (name "Net-(IC12-TNKB2)") (class "Default")
      (node (ref "C41") (pin "1") (pinfunction "1_1") (pintype "passive"))
      (node (ref "IC12") (pin "7") (pinfunction "TNKB2_7") (pintype "input"))
      (node (ref "L3") (pin "2") (pinfunction "2_2") (pintype "passive"))
      (node (ref "R58") (pin "2") (pinfunction "2_2") (pintype "passive"))
    )
    (net (code "149") (name "Net-(IC25A-O)") (class "Default")
      (node (ref "IC25") (pin "12") (pinfunction "I0_12") (pintype "input"))
      (node (ref "IC25") (pin "3") (pinfunction "O_3") (pintype "output"))
    )
    (net (code "150") (name "Net-(IC25B-I1)") (class "Default")
      (node (ref "IC25") (pin "10") (pinfunction "I1_10") (pintype "input"))
      (node (ref "IC25") (pin "5") (pinfunction "I1_5") (pintype "input"))
      (node (ref "IC28") (pin "4") (pinfunction "O_4") (pintype "output"))
    )
    (net (code "151") (name "Net-(IC25C-I0)") (class "Default")
      (node (ref "IC25") (pin "9") (pinfunction "I0_9") (pintype "input"))
      (node (ref "IC28") (pin "2") (pinfunction "O_2") (pintype "output"))
    )
    (net (code "152") (name "Net-(IC25D-O)") (class "Default")
      (node (ref "IC25") (pin "11") (pinfunction "O_11") (pintype "output"))
      (node (ref "IC27") (pin "1") (pinfunction "I0_1") (pintype "input"))
    )
    (net (code "153") (name "Net-(IC26A-O)") (class "Default")
      (node (ref "IC26") (pin "3") (pinfunction "O_3") (pintype "output"))
      (node (ref "IC26") (pin "4") (pinfunction "I0_4") (pintype "input"))
    )
    (net (code "154") (name "Net-(IC26B-I1)") (class "Default")
      (node (ref "IC26") (pin "5") (pinfunction "I1_5") (pintype "input"))
      (node (ref "IC5") (pin "5") (pinfunction "Q_5") (pintype "output"))
    )
    (net (code "155") (name "Net-(IC26B-O)") (class "Default")
      (node (ref "IC26") (pin "6") (pinfunction "O_6") (pintype "output"))
      (node (ref "IC26") (pin "9") (pinfunction "I0_9") (pintype "input"))
    )
    (net (code "156") (name "Net-(IC26C-I1)") (class "Default")
      (node (ref "IC26") (pin "10") (pinfunction "I1_10") (pintype "input"))
      (node (ref "IC26") (pin "11") (pinfunction "O_11") (pintype "output"))
    )
    (net (code "157") (name "Net-(IC27A-I1)") (class "Default")
      (node (ref "C10") (pin "1") (pinfunction "1_1") (pintype "passive"))
      (node (ref "IC27") (pin "2") (pinfunction "I1_2") (pintype "input"))
      (node (ref "R28") (pin "2") (pinfunction "2_2") (pintype "passive"))
    )
    (net (code "158") (name "Net-(IC27C-I1)") (class "Default")
      (node (ref "C11") (pin "1") (pinfunction "1_1") (pintype "passive"))
      (node (ref "IC27") (pin "10") (pinfunction "I1_10") (pintype "input"))
      (node (ref "R45") (pin "2") (pinfunction "2_2") (pintype "passive"))
    )
    (net (code "159") (name "Net-(IC27C-O)") (class "Default")
      (node (ref "IC27") (pin "8") (pinfunction "O_8") (pintype "output"))
      (node (ref "IC28") (pin "3") (pinfunction "I_3") (pintype "input"))
    )
    (net (code "160") (name "Net-(IC28C-I)") (class "Default")
      (node (ref "IC28") (pin "5") (pinfunction "I_5") (pintype "input"))
      (node (ref "IC3") (pin "35") (pinfunction "GATE_35") (pintype "output"))
      (node (ref "IC4") (pin "11") (pinfunction "CLK_11") (pintype "input"))
    )
    (net (code "161") (name "Net-(IC28D-I)") (class "Default")
      (node (ref "C6") (pin "2") (pinfunction "2_2") (pintype "passive"))
      (node (ref "C7") (pin "2") (pinfunction "2_2") (pintype "passive"))
      (node (ref "IC28") (pin "9") (pinfunction "I_9") (pintype "input"))
      (node (ref "Q3") (pin "C") (pinfunction "C_C") (pintype "passive"))
      (node (ref "R43") (pin "1") (pinfunction "1_1") (pintype "passive"))
      (node (ref "R44") (pin "1") (pinfunction "1_1") (pintype "passive"))
    )
    (net (code "162") (name "Net-(IC28D-O)") (class "Default")
      (node (ref "IC28") (pin "11") (pinfunction "I_11") (pintype "input"))
      (node (ref "IC28") (pin "8") (pinfunction "O_8") (pintype "output"))
      (node (ref "JP") (pin "3") (pinfunction "3_3") (pintype "passive"))
    )
    (net (code "163") (name "Net-(IC28E-O)") (class "Default")
      (node (ref "IC28") (pin "10") (pinfunction "O_10") (pintype "output"))
      (node (ref "IC3") (pin "11") (pinfunction "CLK_11") (pintype "input"))
      (node (ref "JP") (pin "1") (pinfunction "1_1") (pintype "passive"))
      (node (ref "JP") (pin "2") (pinfunction "2_2") (pintype "passive"))
      (node (ref "TP2") (pin "TP") (pinfunction "TP_TP") (pintype "input"))
    )
    (net (code "164") (name "Net-(J4-Pad2)") (class "Default")
      (node (ref "J4") (pin "2") (pinfunction "2_2") (pintype "passive"))
      (node (ref "MIC") (pin "TIP") (pinfunction "TIP_TIP") (pintype "passive"))
    )
    (net (code "165") (name "Net-(MIC-PadNC)") (class "Default")
      (node (ref "MIC") (pin "NC") (pinfunction "NC_NC") (pintype "passive"))
      (node (ref "R46") (pin "1") (pinfunction "1_1") (pintype "passive"))
      (node (ref "R69") (pin "2") (pinfunction "2_2") (pintype "passive"))
    )
    (net (code "166") (name "Net-(PE-M)") (class "Default")
      (node (ref "D6") (pin "A") (pinfunction "A_A") (pintype "bidirectional"))
      (node (ref "KB2") (pin "5") (pinfunction "5_5") (pintype "passive"))
      (node (ref "P") (pin "5") (pinfunction "M_5") (pintype "passive"))
      (node (ref "P") (pin "8") (pinfunction "M_8") (pintype "passive"))
      (node (ref "P") (pin "9") (pinfunction "M_9") (pintype "passive"))
    )
    (net (code "167") (name "Net-(PG-M)") (class "Default")
      (node (ref "D5") (pin "A") (pinfunction "A_A") (pintype "bidirectional"))
      (node (ref "KB2") (pin "8") (pinfunction "8_8") (pintype "passive"))
      (node (ref "P") (pin "7") (pinfunction "M_7") (pintype "passive"))
    )
    (net (code "168") (name "Net-(Q2-B)") (class "Default")
      (node (ref "C9") (pin "1") (pinfunction "1_1") (pintype "passive"))
      (node (ref "Q2") (pin "2") (pinfunction "B_2") (pintype "passive"))
      (node (ref "R49") (pin "1") (pinfunction "1_1") (pintype "passive"))
      (node (ref "R50") (pin "2") (pinfunction "2_2") (pintype "passive"))
    )
    (net (code "169") (name "Net-(Q3-PadE)") (class "Default")
      (node (ref "Q3") (pin "E") (pinfunction "E_E") (pintype "passive"))
      (node (ref "R47") (pin "2") (pinfunction "2_2") (pintype "passive"))
    )
    (net (code "170") (name "Net-(Q4-B)") (class "Default")
      (node (ref "C47") (pin "2") (pinfunction "2_2") (pintype "passive"))
      (node (ref "Q4") (pin "2") (pinfunction "B_2") (pintype "passive"))
      (node (ref "R64") (pin "1") (pinfunction "1_1") (pintype "passive"))
      (node (ref "R65") (pin "1") (pinfunction "1_1") (pintype "passive"))
    )
    (net (code "171") (name "Net-(Q4-C)") (class "Default")
      (node (ref "Q4") (pin "3") (pinfunction "C_3") (pintype "passive"))
      (node (ref "Q5") (pin "B") (pinfunction "B_B") (pintype "passive"))
      (node (ref "Q6") (pin "B") (pinfunction "B_B") (pintype "passive"))
      (node (ref "R66") (pin "2") (pinfunction "2_2") (pintype "passive"))
    )
    (net (code "172") (name "Net-(Q8-E)") (class "Default")
      (node (ref "Q8") (pin "1") (pinfunction "E_1") (pintype "passive"))
      (node (ref "R76") (pin "1") (pinfunction "1_1") (pintype "passive"))
      (node (ref "R77") (pin "1") (pinfunction "1_1") (pintype "passive"))
    )
    (net (code "173") (name "Net-(U$1Y-EDGE)") (class "Default")
      (node (ref "C55") (pin "2") (pinfunction "2_2") (pintype "passive"))
      (node (ref "U$1") (pin "4B") (pinfunction "EDGE_4B") (pintype "bidirectional"))
    )
    (net (code "174") (name "V+") (class "Default")
      (node (ref "7805") (pin "IN") (pinfunction "IN_IN") (pintype "input"))
      (node (ref "C2") (pin "+") (pinfunction "+_+") (pintype "passive"))
      (node (ref "C3") (pin "2") (pinfunction "2_2") (pintype "passive"))
      (node (ref "D22") (pin "A") (pinfunction "A_A") (pintype "bidirectional"))
      (node (ref "J2") (pin "3") (pinfunction "3_3") (pintype "passive"))
      (node (ref "Q5") (pin "C") (pinfunction "C_C") (pintype "passive"))
      (node (ref "R66") (pin "1") (pinfunction "1_1") (pintype "passive"))
      (node (ref "U$1") (pin "4A") (pinfunction "EDGE_4A") (pintype "bidirectional"))
      (node (ref "X2") (pin "NC") (pinfunction "NC_NC") (pintype "passive"))
      (node (ref "X2") (pin "TIP") (pinfunction "TIP_TIP") (pintype "passive"))
    )
    (net (code "175") (name "VDD") (class "Default")
      (node (ref "C23") (pin "1") (pinfunction "1_1") (pintype "passive"))
      (node (ref "C25") (pin "1") (pinfunction "1_1") (pintype "passive"))
      (node (ref "C28") (pin "1") (pinfunction "1_1") (pintype "passive"))
      (node (ref "C30") (pin "1") (pinfunction "1_1") (pintype "passive"))
      (node (ref "IC13") (pin "8") (pinfunction "VDD_8") (pintype "power_in"))
      (node (ref "IC14") (pin "8") (pinfunction "VDD_8") (pintype "power_in"))
      (node (ref "IC15") (pin "8") (pinfunction "VDD_8") (pintype "power_in"))
      (node (ref "IC16") (pin "8") (pinfunction "VDD_8") (pintype "power_in"))
      (node (ref "IC17") (pin "8") (pinfunction "VDD_8") (pintype "power_in"))
      (node (ref "IC18") (pin "8") (pinfunction "VDD_8") (pintype "power_in"))
      (node (ref "IC19") (pin "8") (pinfunction "VDD_8") (pintype "power_in"))
      (node (ref "IC20") (pin "8") (pinfunction "VDD_8") (pintype "power_in"))
      (node (ref "J2") (pin "2") (pinfunction "2_2") (pintype "passive"))
    )
    (net (code "176") (name "unconnected-(IC3-~{50}{slash}60HZ-Pad1)") (class "Default")
      (node (ref "IC3") (pin "1") (pinfunction "~{50}/60HZ_1") (pintype "input"))
    )
    (net (code "177") (name "unconnected-(IC4A-CLK-Pad3)") (class "Default")
      (node (ref "IC4") (pin "3") (pinfunction "CLK_3") (pintype "input"))
    )
    (net (code "178") (name "unconnected-(IC4A-CLR-Pad1)") (class "Default")
      (node (ref "IC4") (pin "1") (pinfunction "CLR_1") (pintype "input"))
    )
    (net (code "179") (name "unconnected-(IC4A-D-Pad2)") (class "Default")
      (node (ref "IC4") (pin "2") (pinfunction "D_2") (pintype "input"))
    )
    (net (code "180") (name "unconnected-(IC4A-PRE-Pad4)") (class "Default")
      (node (ref "IC4") (pin "4") (pinfunction "PRE_4") (pintype "input"))
    )
    (net (code "181") (name "unconnected-(IC4A-Q-Pad5)") (class "Default")
      (node (ref "IC4") (pin "5") (pinfunction "Q_5") (pintype "output"))
    )
    (net (code "182") (name "unconnected-(IC4A-~{Q}-Pad6)") (class "Default")
      (node (ref "IC4") (pin "6") (pinfunction "~{Q}_6") (pintype "output"))
    )
    (net (code "183") (name "unconnected-(IC5B-~{Q}-Pad8)") (class "Default")
      (node (ref "IC5") (pin "8") (pinfunction "~{Q}_8") (pintype "output"))
    )
    (net (code "184") (name "unconnected-(IC6A-1A-Pad2)") (class "Default")
      (node (ref "IC6") (pin "2") (pinfunction "1A_2") (pintype "input"))
    )
    (net (code "185") (name "unconnected-(IC6A-1B-Pad3)") (class "Default")
      (node (ref "IC6") (pin "3") (pinfunction "1B_3") (pintype "input"))
    )
    (net (code "186") (name "unconnected-(IC6A-1Y-Pad4)") (class "Default")
      (node (ref "IC6") (pin "4") (pinfunction "1Y_4") (pintype "output"))
    )
    (net (code "187") (name "unconnected-(IC6A-3A-Pad11)") (class "Default")
      (node (ref "IC6") (pin "11") (pinfunction "3A_11") (pintype "input"))
    )
    (net (code "188") (name "unconnected-(IC6A-3B-Pad10)") (class "Default")
      (node (ref "IC6") (pin "10") (pinfunction "3B_10") (pintype "input"))
    )
    (net (code "189") (name "unconnected-(IC6A-3Y-Pad9)") (class "Default")
      (node (ref "IC6") (pin "9") (pinfunction "3Y_9") (pintype "output"))
    )
    (net (code "190") (name "unconnected-(IC9A-1A-Pad2)") (class "Default")
      (node (ref "IC9") (pin "2") (pinfunction "1A_2") (pintype "input"))
    )
    (net (code "191") (name "unconnected-(IC9A-1B-Pad3)") (class "Default")
      (node (ref "IC9") (pin "3") (pinfunction "1B_3") (pintype "input"))
    )
    (net (code "192") (name "unconnected-(IC9A-1Y-Pad4)") (class "Default")
      (node (ref "IC9") (pin "4") (pinfunction "1Y_4") (pintype "output"))
    )
    (net (code "193") (name "unconnected-(IC12-CHA_O-Pad11)") (class "Default")
      (node (ref "IC12") (pin "11") (pinfunction "CHA_O_11") (pintype "input"))
    )
    (net (code "194") (name "unconnected-(L1B-S1-PadS2)") (class "Default")
      (node (ref "L1") (pin "S2") (pinfunction "S1_S2") (pintype "passive"))
    )
    (net (code "195") (name "unconnected-(L1B-S2-PadS1)") (class "Default")
      (node (ref "L1") (pin "S1") (pinfunction "S2_S1") (pintype "passive"))
    )
    (net (code "196") (name "unconnected-(U$1AX-EDGE-Pad28B)") (class "Default")
      (node (ref "U$1") (pin "28B") (pinfunction "EDGE_28B") (pintype "bidirectional"))
    )
    (net (code "197") (name "unconnected-(U$1F-EDGE-Pad15A)") (class "Default")
      (node (ref "U$1") (pin "15A") (pinfunction "EDGE_15A") (pintype "bidirectional"))
    )
    (net (code "198") (name "unconnected-(U$1G-EDGE-Pad16A)") (class "Default")
      (node (ref "U$1") (pin "16A") (pinfunction "EDGE_16A") (pintype "bidirectional"))
    )
    (net (code "199") (name "unconnected-(U$1H-EDGE-Pad17A)") (class "Default")
      (node (ref "U$1") (pin "17A") (pinfunction "EDGE_17A") (pintype "bidirectional"))
    )
    (net (code "200") (name "unconnected-(U$1I-EDGE-Pad18A)") (class "Default")
      (node (ref "U$1") (pin "18A") (pinfunction "EDGE_18A") (pintype "bidirectional"))
    )
  )
)
